# veils_v40.net
KiCad netlist of a schematic drawn in EAGLE
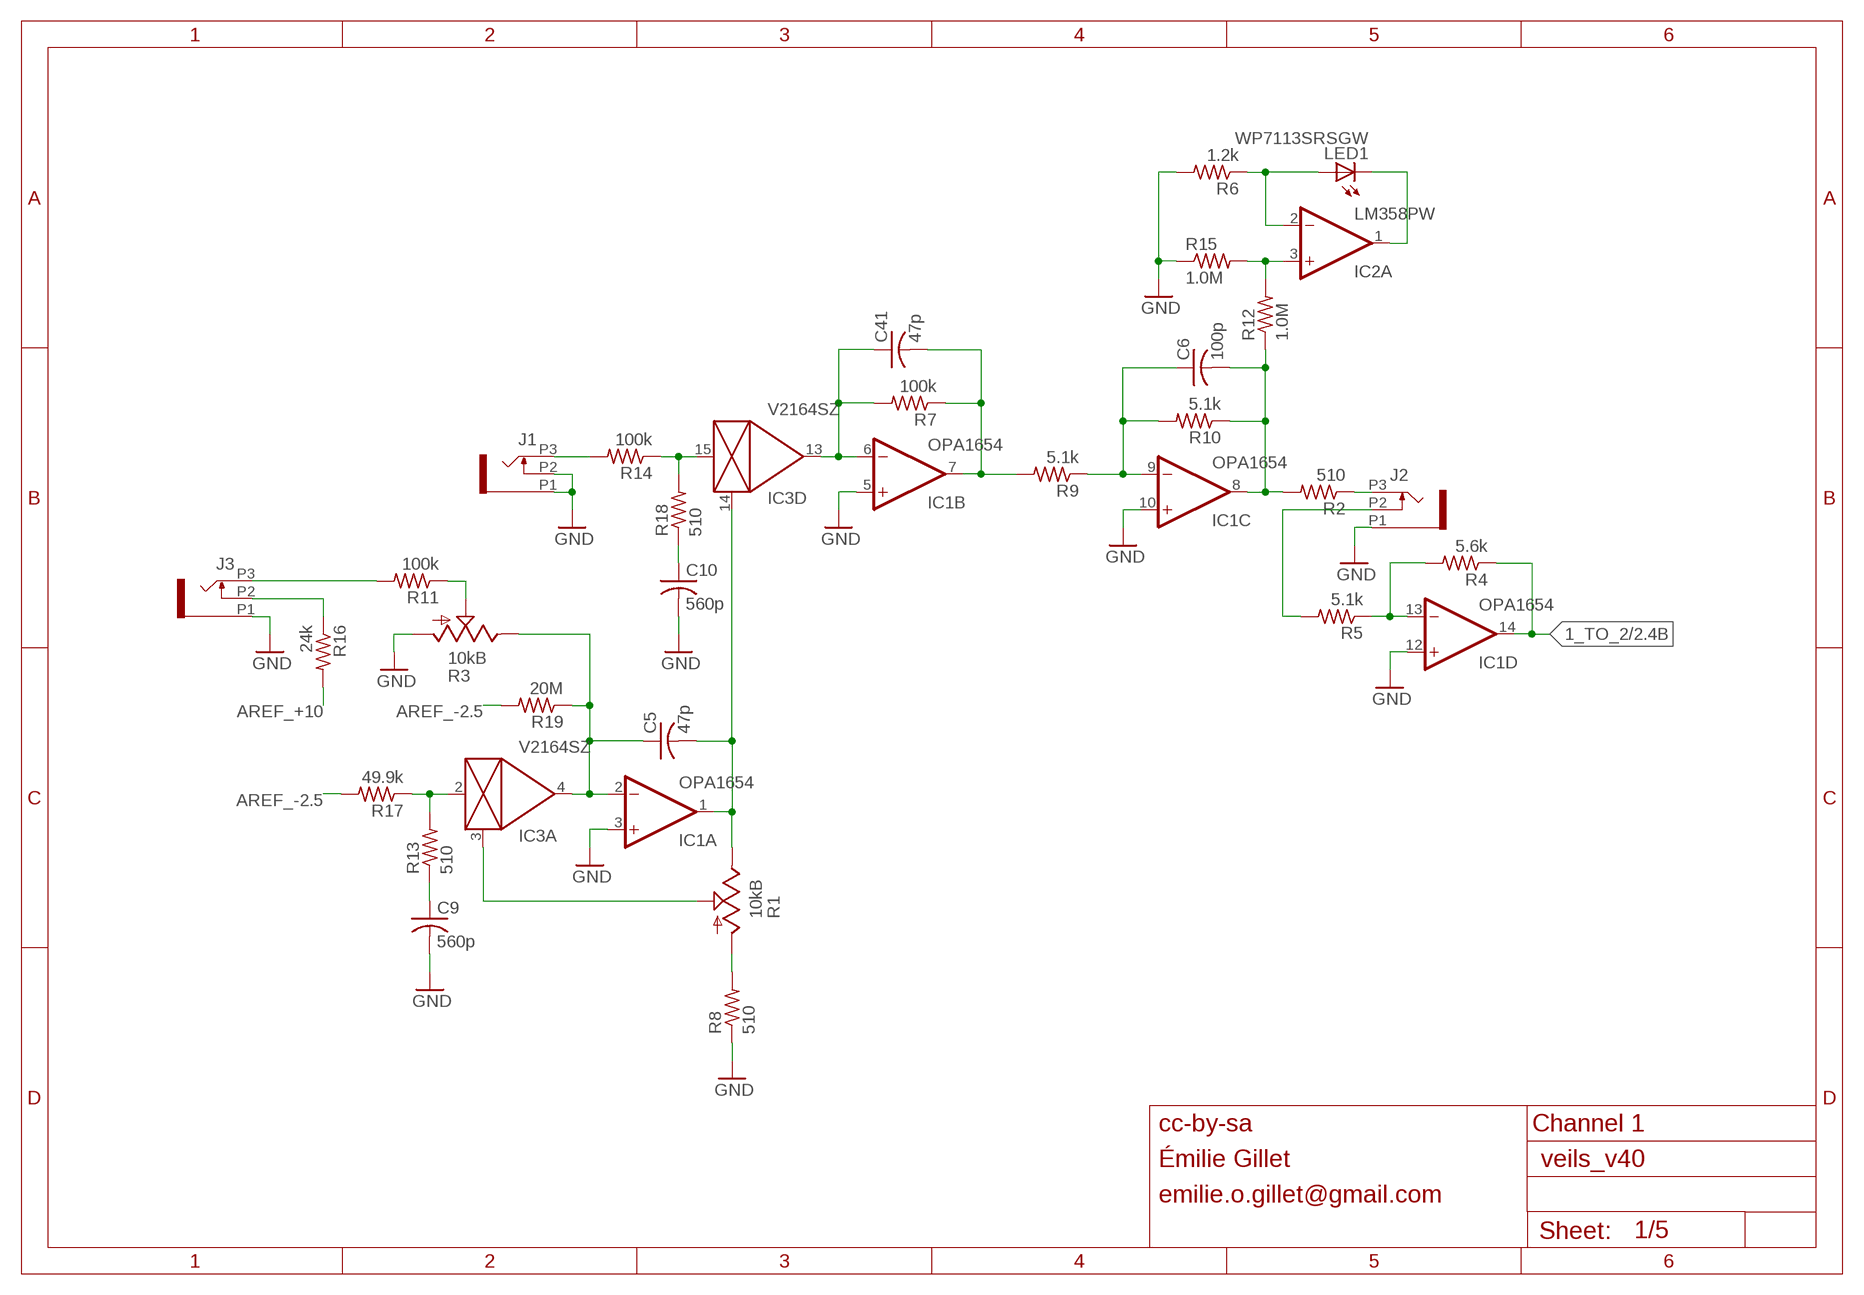
[diagram p0: schematic, sheet 1]
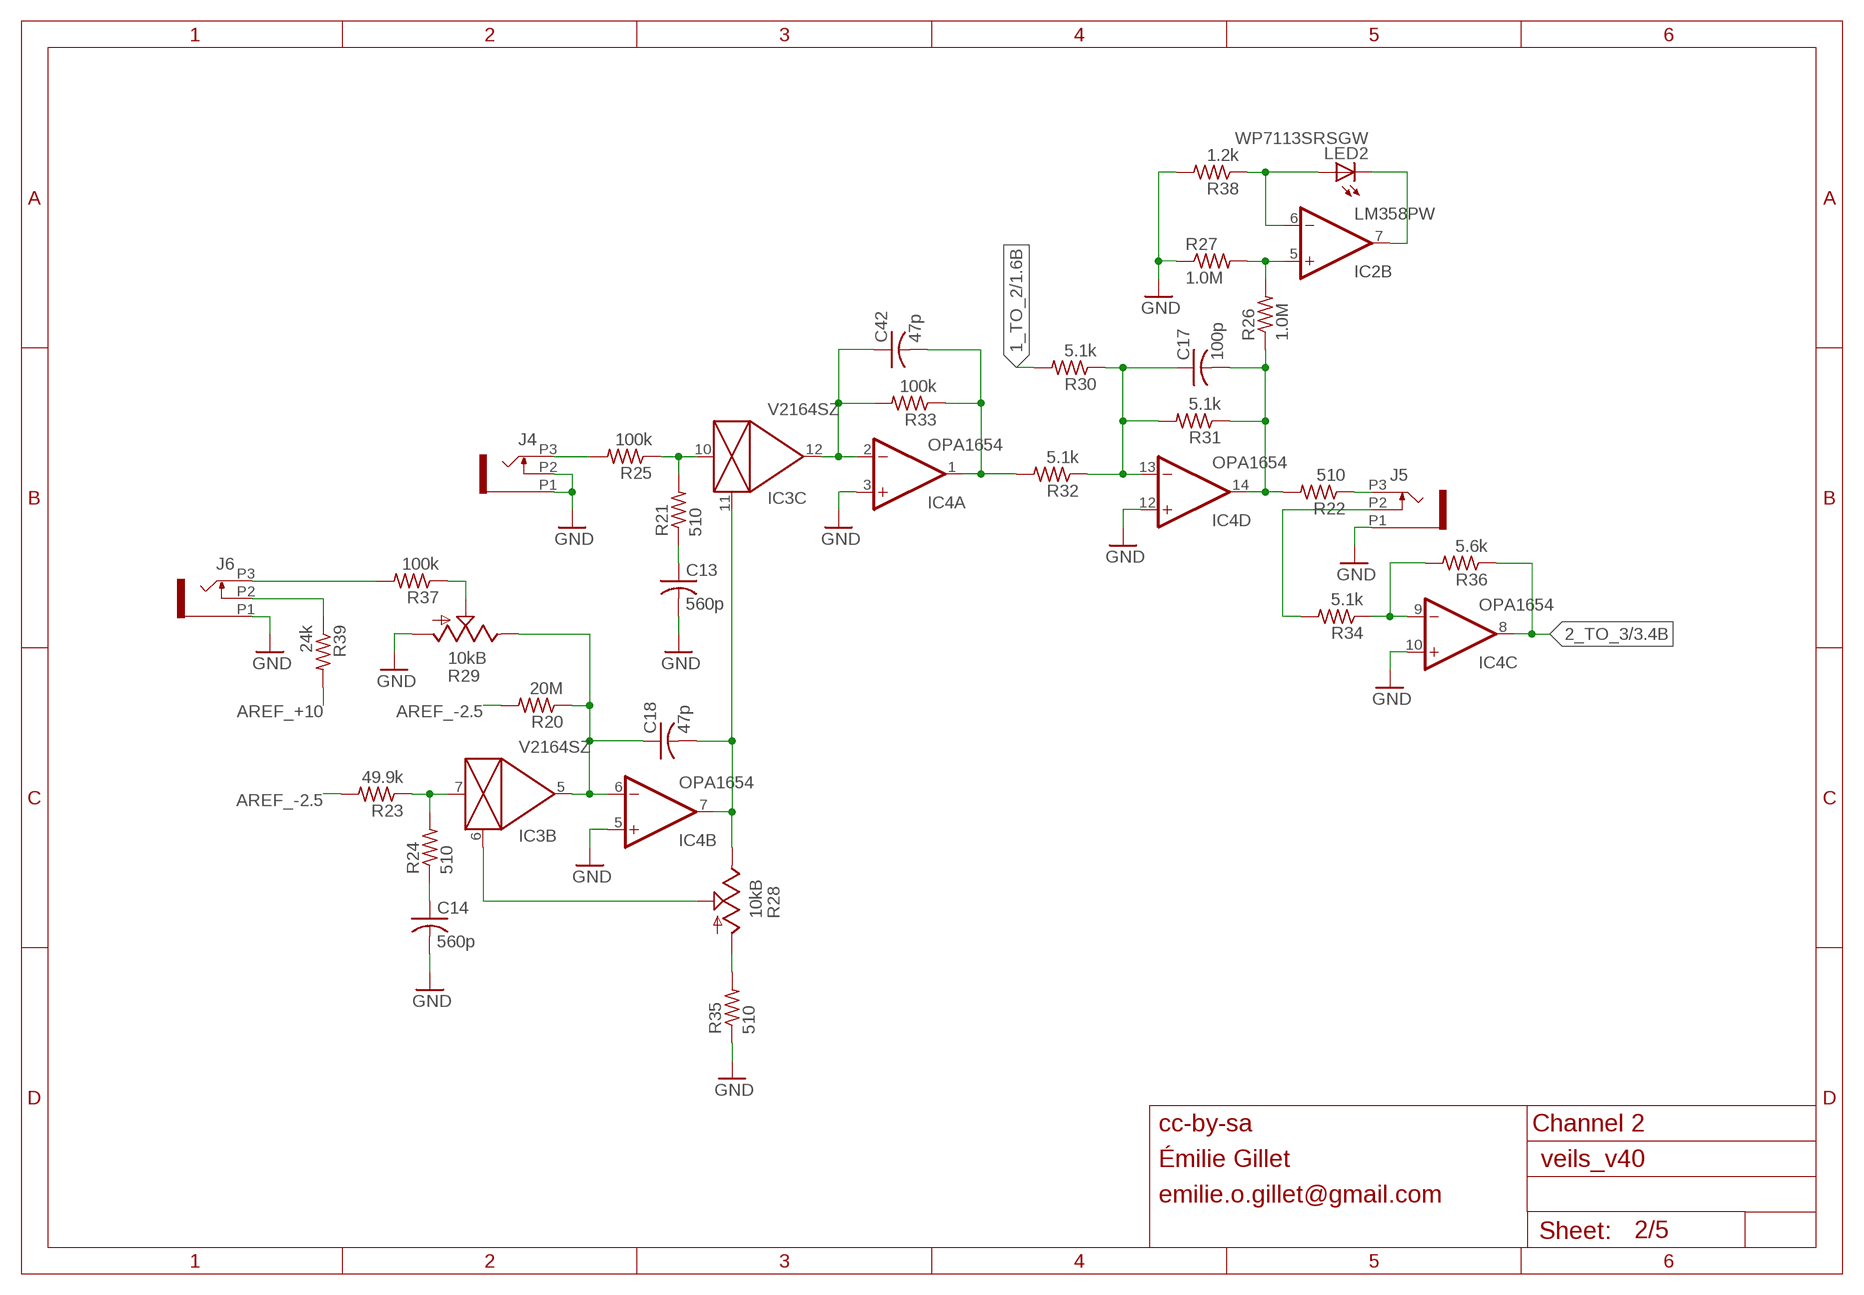
[diagram p1: schematic, sheet 2]
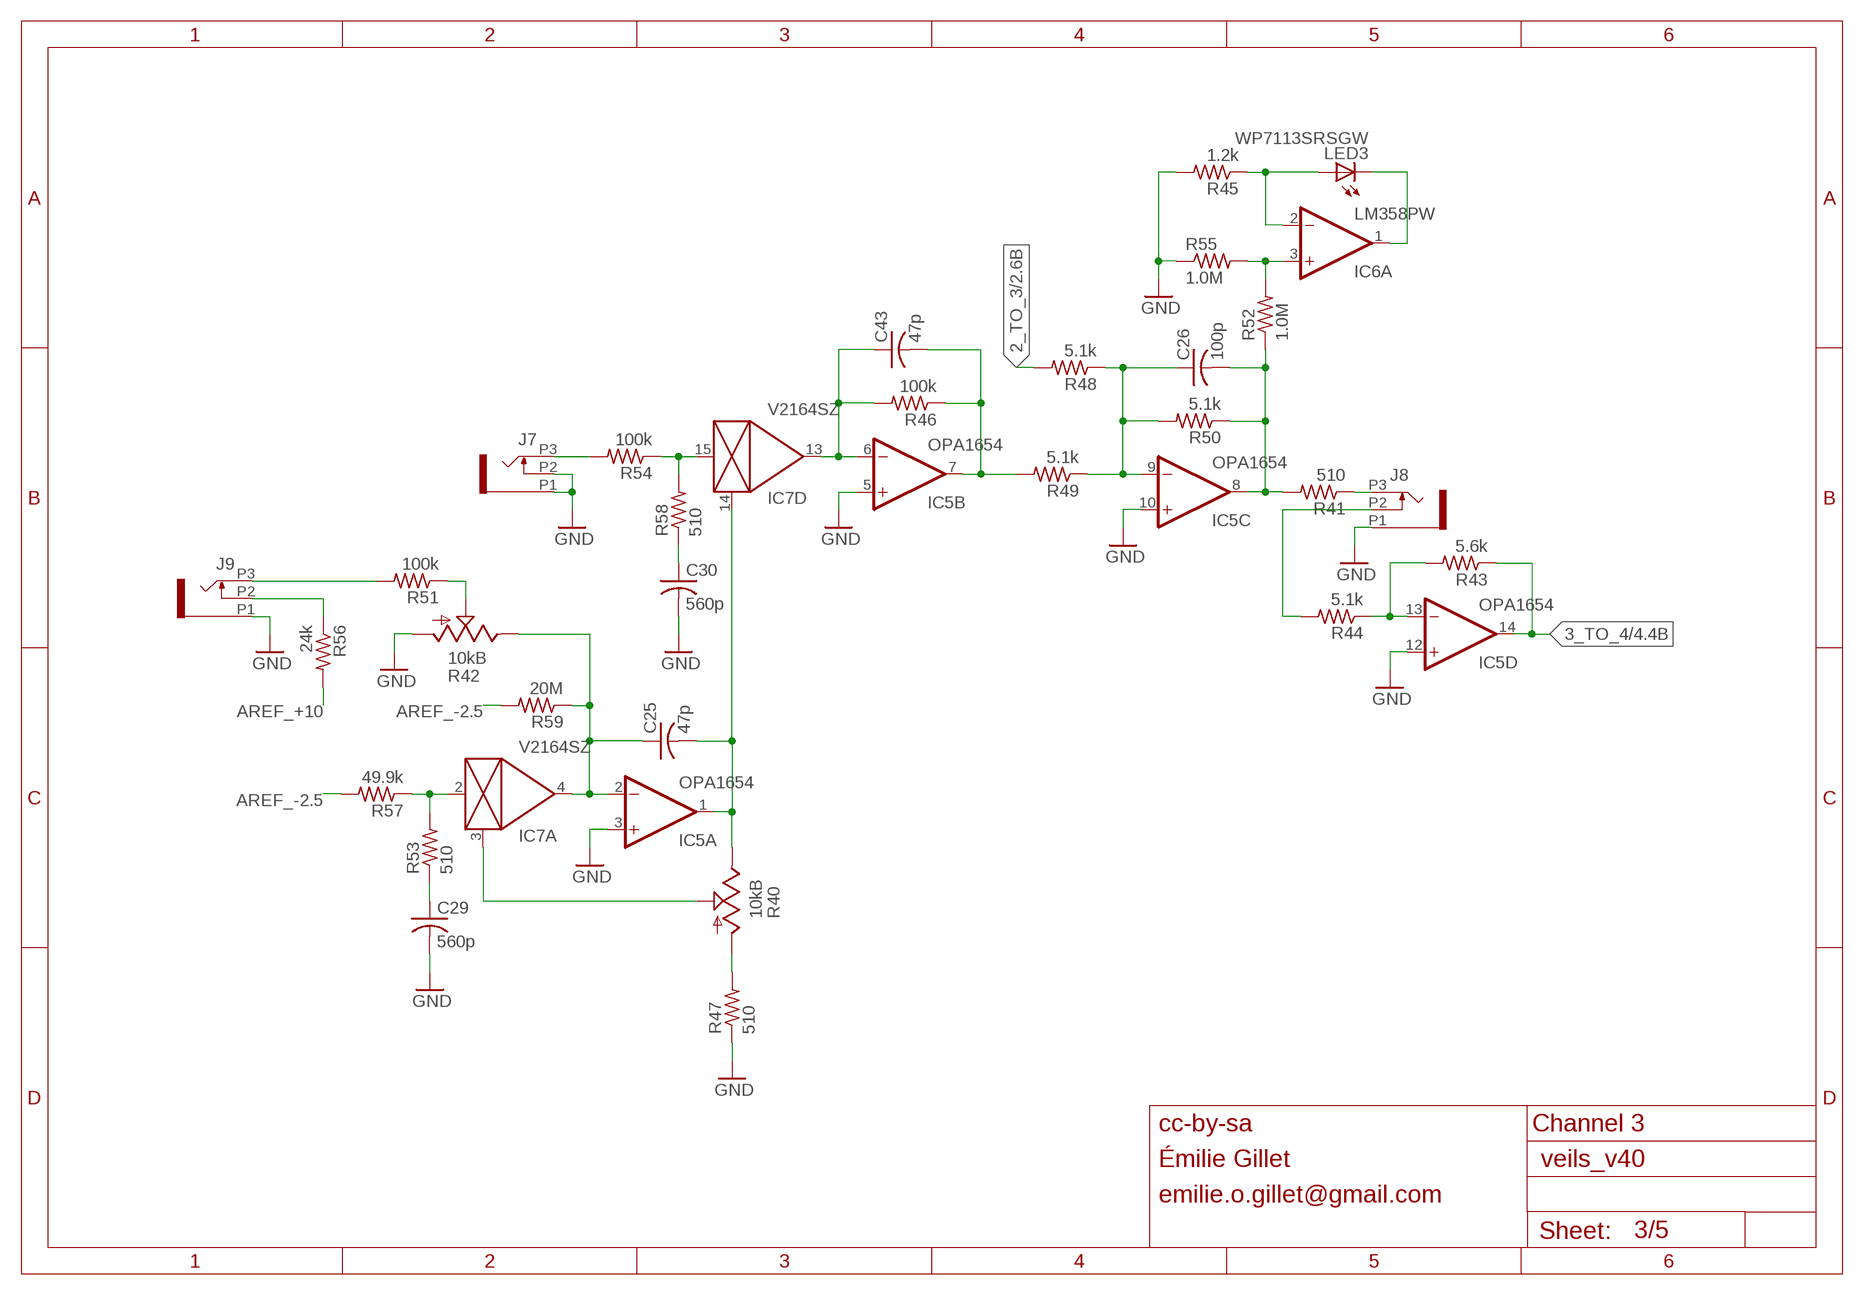
[diagram p2: schematic, sheet 3]
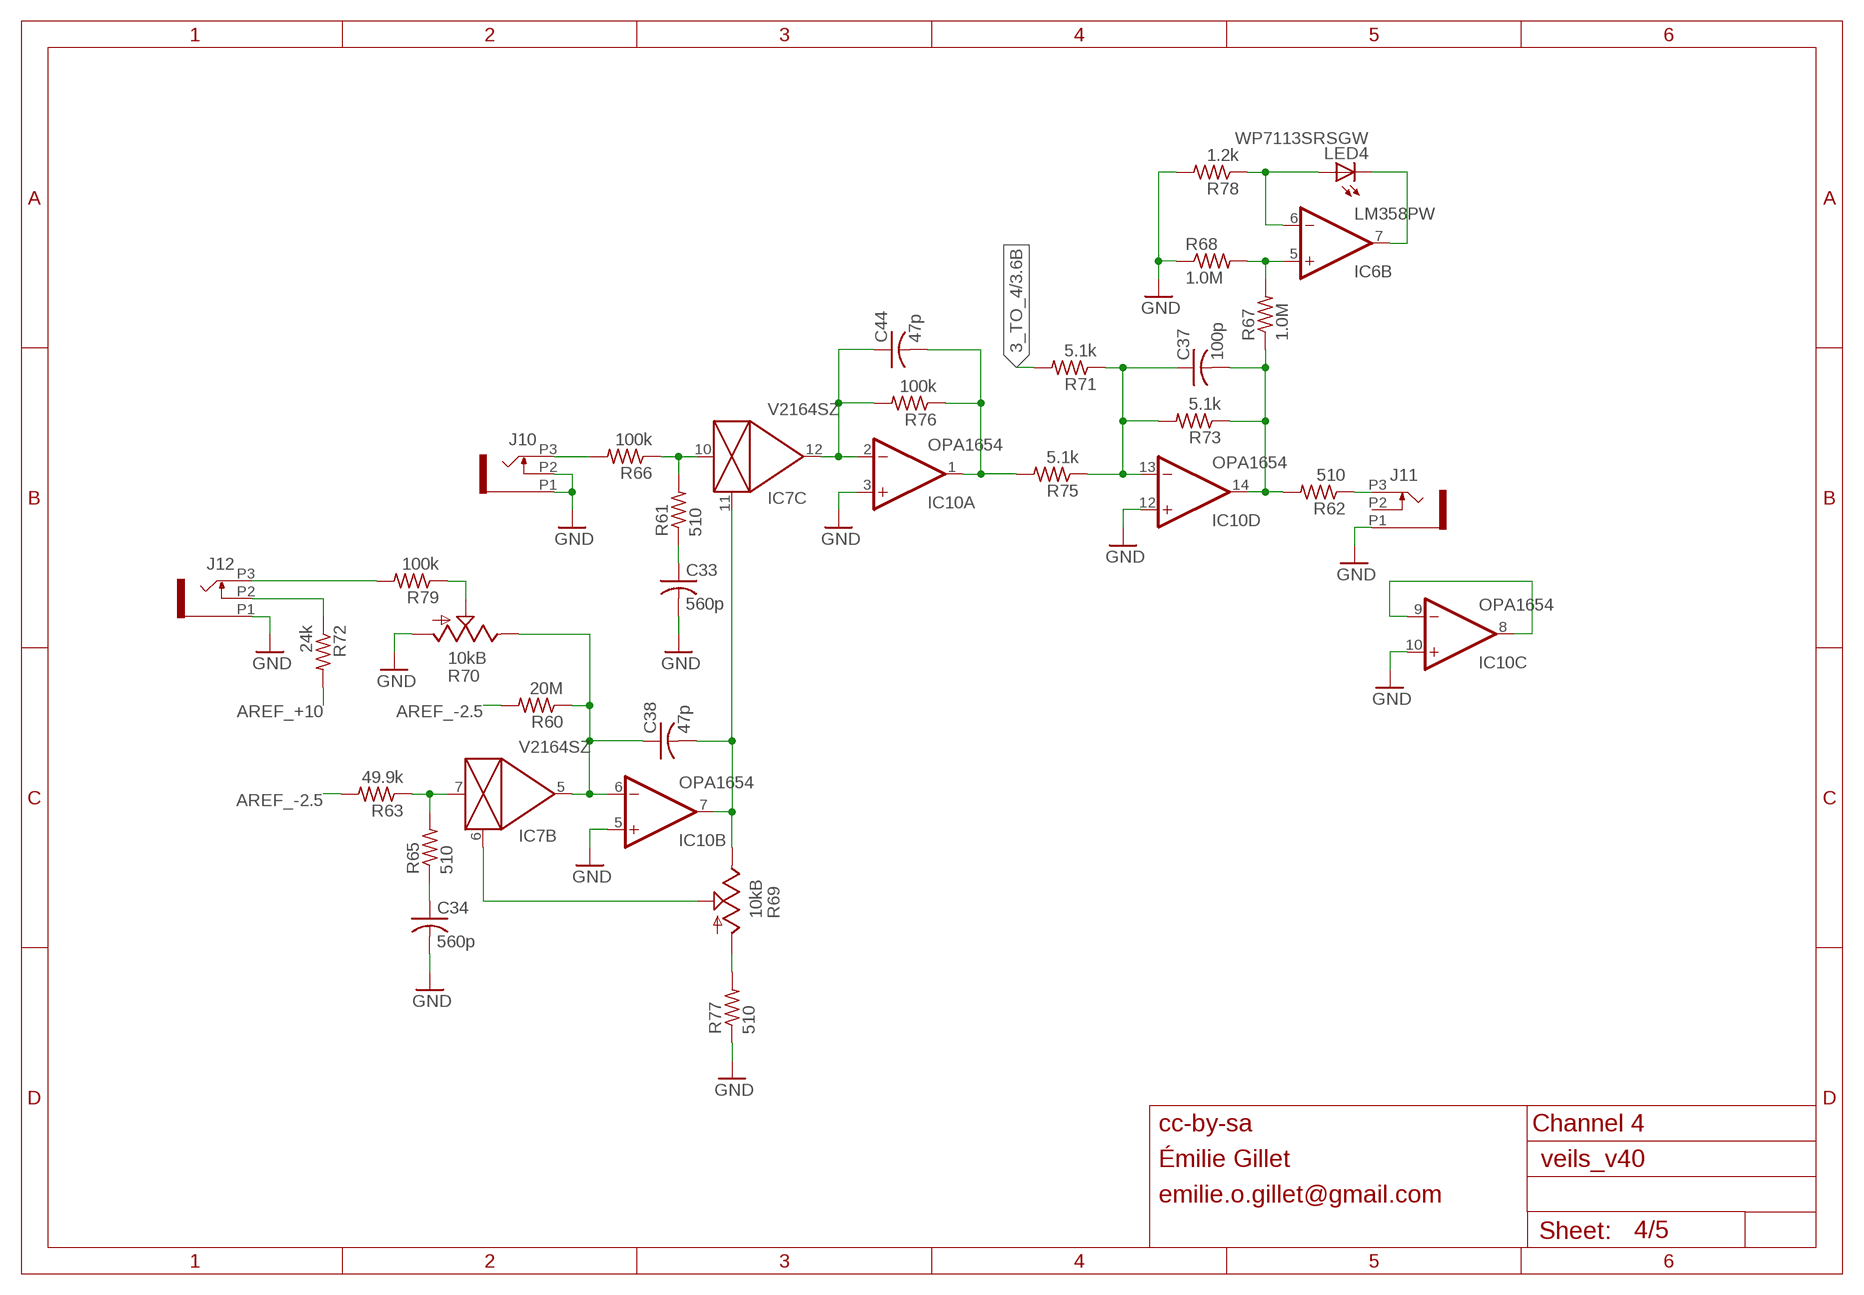
[diagram p3: schematic, sheet 4]
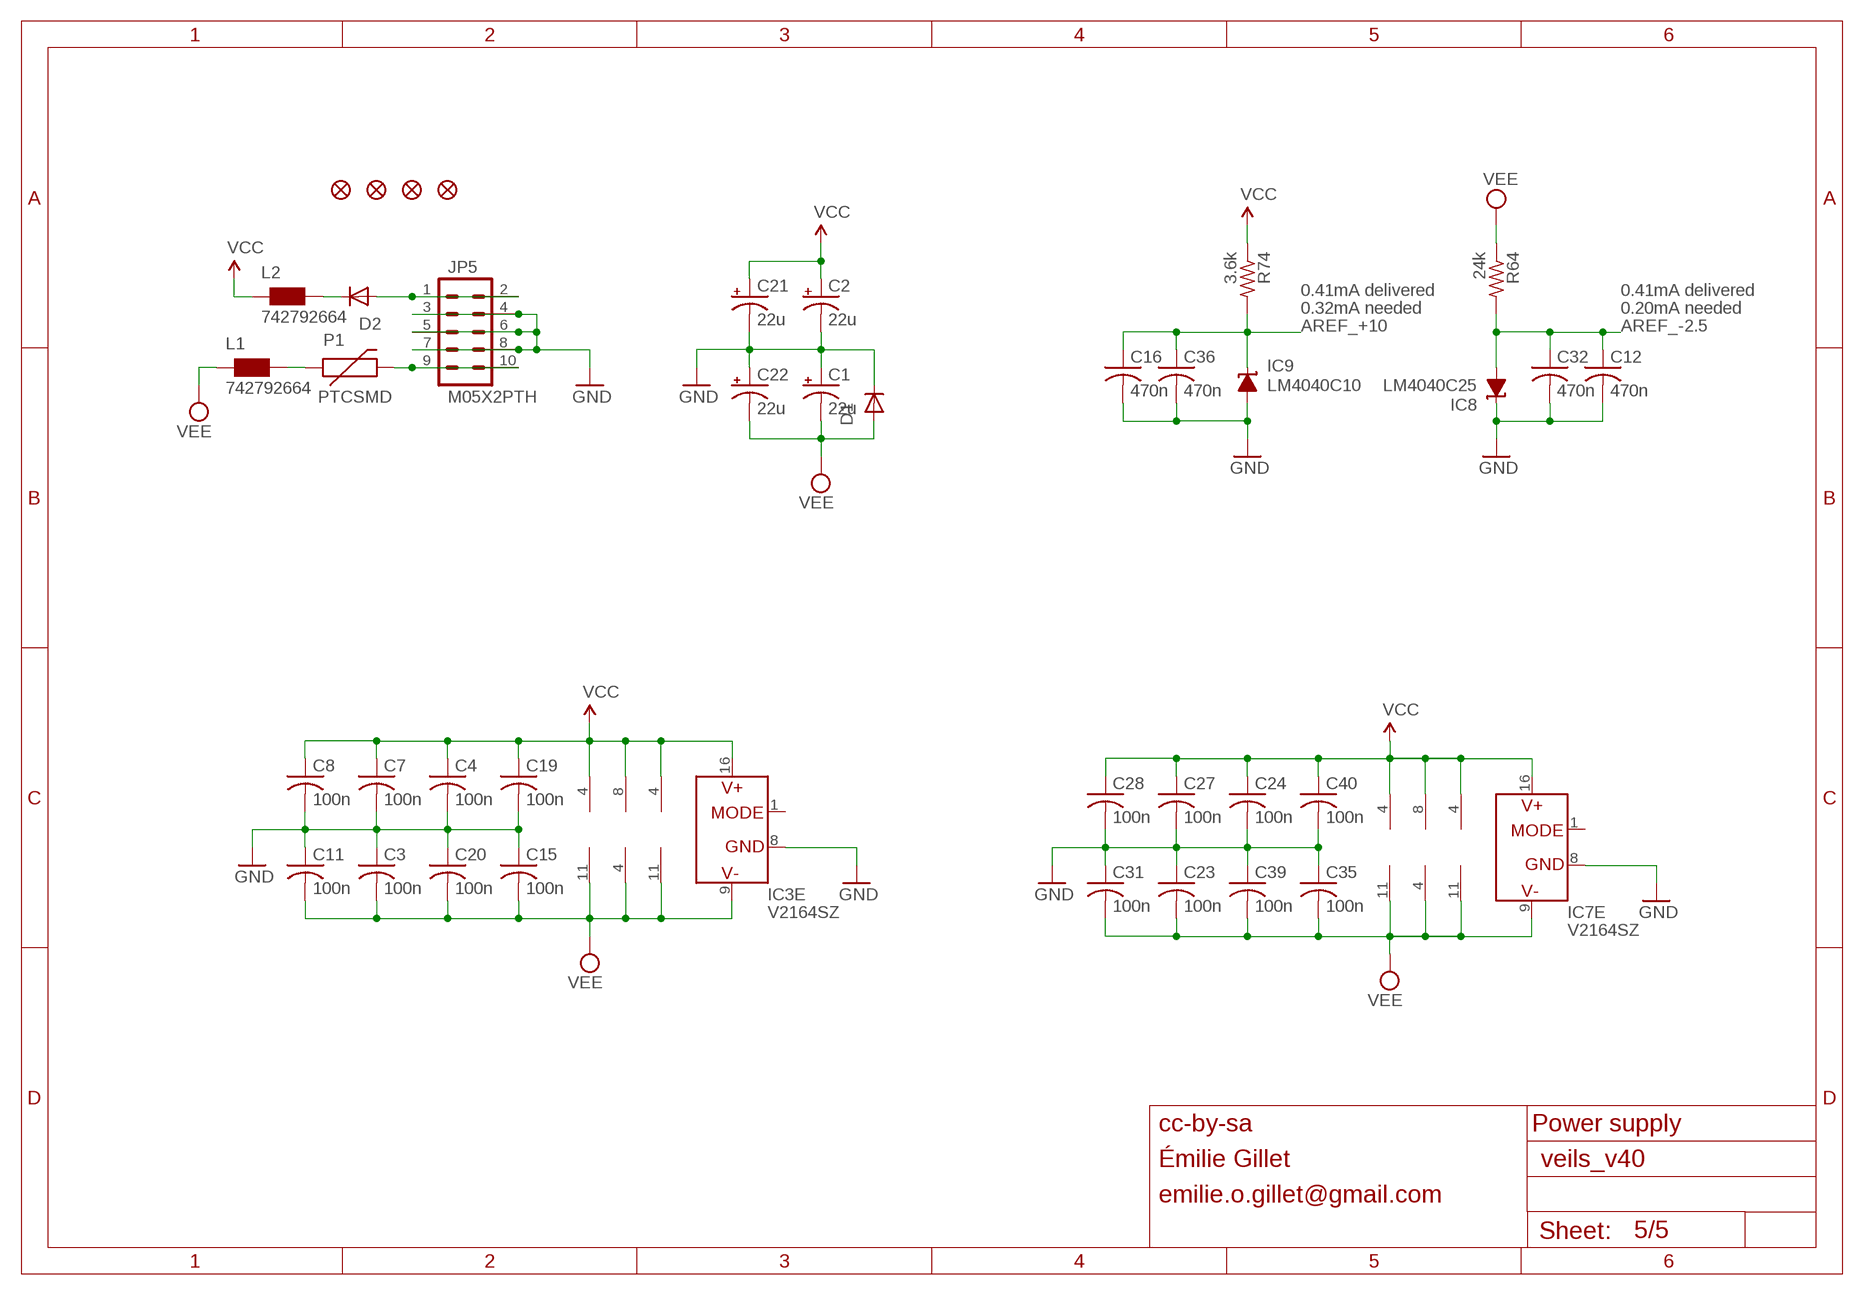
[diagram p4: schematic, sheet 5]

(export (version "E")
  (design (tool "Eeschema 10.0.6"))
  (components
    (comp (ref "C13")
      (value "560p")
      (footprint "eagle-import:C0402")
      (libsource (lib "eagle-import") (part "C-USC0402"))
    )
    (comp (ref "C14")
      (value "560p")
      (footprint "eagle-import:C0402")
      (libsource (lib "eagle-import") (part "C-USC0402"))
    )
    (comp (ref "C17")
      (value "100p")
      (footprint "eagle-import:C0402")
      (libsource (lib "eagle-import") (part "C-USC0402"))
    )
    (comp (ref "C18")
      (value "47p")
      (footprint "eagle-import:C0402")
      (libsource (lib "eagle-import") (part "C-USC0402"))
    )
    (comp (ref "C42")
      (value "47p")
      (footprint "eagle-import:C0402")
      (libsource (lib "eagle-import") (part "C-USC0402"))
    )
    (comp (ref "IC2")
      (value "LM358PW")
      (footprint "eagle-import:TSSOP8")
      (libsource (lib "eagle-import") (part "TL072PW"))
    )
    (comp (ref "IC3")
      (value "V2164SZ")
      (footprint "eagle-import:SOIC16N")
      (libsource (lib "eagle-import") (part "SSM2164S"))
    )
    (comp (ref "IC4")
      (value "OPA1654")
      (footprint "eagle-import:TSSOP14")
      (libsource (lib "eagle-import") (part "TL074PW"))
    )
    (comp (ref "J4")
      (value "PJ301_THONKICONN6")
      (footprint "eagle-import:WQP_PJ_301M6")
      (libsource (lib "eagle-import") (part "PJ301_THONKICONN6"))
    )
    (comp (ref "J5")
      (value "PJ301_THONKICONN6")
      (footprint "eagle-import:WQP_PJ_301M6")
      (libsource (lib "eagle-import") (part "PJ301_THONKICONN6"))
    )
    (comp (ref "J6")
      (value "PJ301_THONKICONN6")
      (footprint "eagle-import:WQP_PJ_301M6")
      (libsource (lib "eagle-import") (part "PJ301_THONKICONN6"))
    )
    (comp (ref "LED2")
      (value "WP7113SRSGW")
      (footprint "eagle-import:LED5MM")
      (libsource (lib "eagle-import") (part "LED5MM"))
    )
    (comp (ref "R20")
      (value "20M")
      (footprint "eagle-import:R0402")
      (libsource (lib "eagle-import") (part "R-US_R0402"))
    )
    (comp (ref "R21")
      (value "510")
      (footprint "eagle-import:R0402")
      (libsource (lib "eagle-import") (part "R-US_R0402"))
    )
    (comp (ref "R22")
      (value "510")
      (footprint "eagle-import:R0402")
      (libsource (lib "eagle-import") (part "R-US_R0402"))
    )
    (comp (ref "R23")
      (value "49.9k")
      (footprint "eagle-import:R0402")
      (libsource (lib "eagle-import") (part "R-US_R0402"))
    )
    (comp (ref "R24")
      (value "510")
      (footprint "eagle-import:R0402")
      (libsource (lib "eagle-import") (part "R-US_R0402"))
    )
    (comp (ref "R25")
      (value "100k")
      (footprint "eagle-import:R0402")
      (libsource (lib "eagle-import") (part "R-US_R0402"))
    )
    (comp (ref "R26")
      (value "1.0M")
      (footprint "eagle-import:R0402")
      (libsource (lib "eagle-import") (part "R-US_R0402"))
    )
    (comp (ref "R27")
      (value "1.0M")
      (footprint "eagle-import:R0402")
      (libsource (lib "eagle-import") (part "R-US_R0402"))
    )
    (comp (ref "R28")
      (value "10kB")
      (footprint "eagle-import:ALPS_POT_VERTICAL")
      (libsource (lib "eagle-import") (part "POT_USVERTICAL"))
    )
    (comp (ref "R29")
      (value "10kB")
      (footprint "eagle-import:ALPS_POT_VERTICAL_PS")
      (libsource (lib "eagle-import") (part "pot-alps_POT_USVERTICAL_PS"))
    )
    (comp (ref "R30")
      (value "5.1k")
      (footprint "eagle-import:R0402")
      (libsource (lib "eagle-import") (part "R-US_R0402"))
    )
    (comp (ref "R31")
      (value "5.1k")
      (footprint "eagle-import:R0402")
      (libsource (lib "eagle-import") (part "R-US_R0402"))
    )
    (comp (ref "R32")
      (value "5.1k")
      (footprint "eagle-import:R0402")
      (libsource (lib "eagle-import") (part "R-US_R0402"))
    )
    (comp (ref "R33")
      (value "100k")
      (footprint "eagle-import:R0402")
      (libsource (lib "eagle-import") (part "R-US_R0402"))
    )
    (comp (ref "R34")
      (value "5.1k")
      (footprint "eagle-import:R0402")
      (libsource (lib "eagle-import") (part "R-US_R0402"))
    )
    (comp (ref "R35")
      (value "510")
      (footprint "eagle-import:R0402")
      (libsource (lib "eagle-import") (part "R-US_R0402"))
    )
    (comp (ref "R36")
      (value "5.6k")
      (footprint "eagle-import:R0402")
      (libsource (lib "eagle-import") (part "R-US_R0402"))
    )
    (comp (ref "R37")
      (value "100k")
      (footprint "eagle-import:R0402")
      (libsource (lib "eagle-import") (part "R-US_R0402"))
    )
    (comp (ref "R38")
      (value "1.2k")
      (footprint "eagle-import:R0402")
      (libsource (lib "eagle-import") (part "R-US_R0402"))
    )
    (comp (ref "R39")
      (value "24k")
      (footprint "eagle-import:R0402")
      (libsource (lib "eagle-import") (part "R-US_R0402"))
    )
    (comp (ref "C5")
      (value "47p")
      (footprint "eagle-import:C0402")
      (libsource (lib "eagle-import") (part "C-USC0402"))
    )
    (comp (ref "C6")
      (value "100p")
      (footprint "eagle-import:C0402")
      (libsource (lib "eagle-import") (part "C-USC0402"))
    )
    (comp (ref "C9")
      (value "560p")
      (footprint "eagle-import:C0402")
      (libsource (lib "eagle-import") (part "C-USC0402"))
    )
    (comp (ref "C10")
      (value "560p")
      (footprint "eagle-import:C0402")
      (libsource (lib "eagle-import") (part "C-USC0402"))
    )
    (comp (ref "C41")
      (value "47p")
      (footprint "eagle-import:C0402")
      (libsource (lib "eagle-import") (part "C-USC0402"))
    )
    (comp (ref "IC1")
      (value "OPA1654")
      (footprint "eagle-import:TSSOP14")
      (libsource (lib "eagle-import") (part "TL074PW"))
    )
    (comp (ref "J1")
      (value "PJ301_THONKICONN6")
      (footprint "eagle-import:WQP_PJ_301M6")
      (libsource (lib "eagle-import") (part "PJ301_THONKICONN6"))
    )
    (comp (ref "J2")
      (value "PJ301_THONKICONN6")
      (footprint "eagle-import:WQP_PJ_301M6")
      (libsource (lib "eagle-import") (part "PJ301_THONKICONN6"))
    )
    (comp (ref "J3")
      (value "PJ301_THONKICONN6")
      (footprint "eagle-import:WQP_PJ_301M6")
      (libsource (lib "eagle-import") (part "PJ301_THONKICONN6"))
    )
    (comp (ref "LED1")
      (value "WP7113SRSGW")
      (footprint "eagle-import:LED5MM")
      (libsource (lib "eagle-import") (part "LED5MM"))
    )
    (comp (ref "R1")
      (value "10kB")
      (footprint "eagle-import:ALPS_POT_VERTICAL")
      (libsource (lib "eagle-import") (part "POT_USVERTICAL"))
    )
    (comp (ref "R2")
      (value "510")
      (footprint "eagle-import:R0402")
      (libsource (lib "eagle-import") (part "R-US_R0402"))
    )
    (comp (ref "R3")
      (value "10kB")
      (footprint "eagle-import:ALPS_POT_VERTICAL_PS")
      (libsource (lib "eagle-import") (part "pot-alps_POT_USVERTICAL_PS"))
    )
    (comp (ref "R4")
      (value "5.6k")
      (footprint "eagle-import:R0402")
      (libsource (lib "eagle-import") (part "R-US_R0402"))
    )
    (comp (ref "R5")
      (value "5.1k")
      (footprint "eagle-import:R0402")
      (libsource (lib "eagle-import") (part "R-US_R0402"))
    )
    (comp (ref "R6")
      (value "1.2k")
      (footprint "eagle-import:R0402")
      (libsource (lib "eagle-import") (part "R-US_R0402"))
    )
    (comp (ref "R7")
      (value "100k")
      (footprint "eagle-import:R0402")
      (libsource (lib "eagle-import") (part "R-US_R0402"))
    )
    (comp (ref "R8")
      (value "510")
      (footprint "eagle-import:R0402")
      (libsource (lib "eagle-import") (part "R-US_R0402"))
    )
    (comp (ref "R9")
      (value "5.1k")
      (footprint "eagle-import:R0402")
      (libsource (lib "eagle-import") (part "R-US_R0402"))
    )
    (comp (ref "R10")
      (value "5.1k")
      (footprint "eagle-import:R0402")
      (libsource (lib "eagle-import") (part "R-US_R0402"))
    )
    (comp (ref "R11")
      (value "100k")
      (footprint "eagle-import:R0402")
      (libsource (lib "eagle-import") (part "R-US_R0402"))
    )
    (comp (ref "R12")
      (value "1.0M")
      (footprint "eagle-import:R0402")
      (libsource (lib "eagle-import") (part "R-US_R0402"))
    )
    (comp (ref "R13")
      (value "510")
      (footprint "eagle-import:R0402")
      (libsource (lib "eagle-import") (part "R-US_R0402"))
    )
    (comp (ref "R14")
      (value "100k")
      (footprint "eagle-import:R0402")
      (libsource (lib "eagle-import") (part "R-US_R0402"))
    )
    (comp (ref "R15")
      (value "1.0M")
      (footprint "eagle-import:R0402")
      (libsource (lib "eagle-import") (part "R-US_R0402"))
    )
    (comp (ref "R16")
      (value "24k")
      (footprint "eagle-import:R0402")
      (libsource (lib "eagle-import") (part "R-US_R0402"))
    )
    (comp (ref "R17")
      (value "49.9k")
      (footprint "eagle-import:R0402")
      (libsource (lib "eagle-import") (part "R-US_R0402"))
    )
    (comp (ref "R18")
      (value "510")
      (footprint "eagle-import:R0402")
      (libsource (lib "eagle-import") (part "R-US_R0402"))
    )
    (comp (ref "R19")
      (value "20M")
      (footprint "eagle-import:R0402")
      (libsource (lib "eagle-import") (part "R-US_R0402"))
    )
    (comp (ref "C1")
      (value "22u")
      (footprint "eagle-import:PANASONIC_B")
      (libsource (lib "eagle-import") (part "CPOL-USB"))
    )
    (comp (ref "C2")
      (value "22u")
      (footprint "eagle-import:PANASONIC_B")
      (libsource (lib "eagle-import") (part "CPOL-USB"))
    )
    (comp (ref "C3")
      (value "100n")
      (footprint "eagle-import:C0402")
      (libsource (lib "eagle-import") (part "C-USC0402"))
    )
    (comp (ref "C4")
      (value "100n")
      (footprint "eagle-import:C0402")
      (libsource (lib "eagle-import") (part "C-USC0402"))
    )
    (comp (ref "C7")
      (value "100n")
      (footprint "eagle-import:C0402")
      (libsource (lib "eagle-import") (part "C-USC0402"))
    )
    (comp (ref "C8")
      (value "100n")
      (footprint "eagle-import:C0402")
      (libsource (lib "eagle-import") (part "C-USC0402"))
    )
    (comp (ref "C11")
      (value "100n")
      (footprint "eagle-import:C0402")
      (libsource (lib "eagle-import") (part "C-USC0402"))
    )
    (comp (ref "C12")
      (value "470n")
      (footprint "eagle-import:C0402")
      (libsource (lib "eagle-import") (part "C-USC0402"))
    )
    (comp (ref "C15")
      (value "100n")
      (footprint "eagle-import:C0402")
      (libsource (lib "eagle-import") (part "C-USC0402"))
    )
    (comp (ref "C16")
      (value "470n")
      (footprint "eagle-import:C0402")
      (libsource (lib "eagle-import") (part "C-USC0402"))
    )
    (comp (ref "C19")
      (value "100n")
      (footprint "eagle-import:C0402")
      (libsource (lib "eagle-import") (part "C-USC0402"))
    )
    (comp (ref "C20")
      (value "100n")
      (footprint "eagle-import:C0402")
      (libsource (lib "eagle-import") (part "C-USC0402"))
    )
    (comp (ref "C21")
      (value "22u")
      (footprint "eagle-import:PANASONIC_B")
      (libsource (lib "eagle-import") (part "CPOL-USB"))
    )
    (comp (ref "C22")
      (value "22u")
      (footprint "eagle-import:PANASONIC_B")
      (libsource (lib "eagle-import") (part "CPOL-USB"))
    )
    (comp (ref "C23")
      (value "100n")
      (footprint "eagle-import:C0402")
      (libsource (lib "eagle-import") (part "C-USC0402"))
    )
    (comp (ref "C24")
      (value "100n")
      (footprint "eagle-import:C0402")
      (libsource (lib "eagle-import") (part "C-USC0402"))
    )
    (comp (ref "C27")
      (value "100n")
      (footprint "eagle-import:C0402")
      (libsource (lib "eagle-import") (part "C-USC0402"))
    )
    (comp (ref "C28")
      (value "100n")
      (footprint "eagle-import:C0402")
      (libsource (lib "eagle-import") (part "C-USC0402"))
    )
    (comp (ref "C31")
      (value "100n")
      (footprint "eagle-import:C0402")
      (libsource (lib "eagle-import") (part "C-USC0402"))
    )
    (comp (ref "C32")
      (value "470n")
      (footprint "eagle-import:C0402")
      (libsource (lib "eagle-import") (part "C-USC0402"))
    )
    (comp (ref "C35")
      (value "100n")
      (footprint "eagle-import:C0402")
      (libsource (lib "eagle-import") (part "C-USC0402"))
    )
    (comp (ref "C36")
      (value "470n")
      (footprint "eagle-import:C0402")
      (libsource (lib "eagle-import") (part "C-USC0402"))
    )
    (comp (ref "C39")
      (value "100n")
      (footprint "eagle-import:C0402")
      (libsource (lib "eagle-import") (part "C-USC0402"))
    )
    (comp (ref "C40")
      (value "100n")
      (footprint "eagle-import:C0402")
      (libsource (lib "eagle-import") (part "C-USC0402"))
    )
    (comp (ref "D1")
      (value "1N5819HW")
      (footprint "eagle-import:SOD123")
      (libsource (lib "eagle-import") (part "DIODE-SOD123"))
    )
    (comp (ref "D2")
      (value "1N5819HW")
      (footprint "eagle-import:SOD123")
      (libsource (lib "eagle-import") (part "DIODE-SOD123"))
    )
    (comp (ref "IC5")
      (value "OPA1654")
      (footprint "eagle-import:TSSOP14")
      (libsource (lib "eagle-import") (part "TL074PW"))
    )
    (comp (ref "IC6")
      (value "LM358PW")
      (footprint "eagle-import:TSSOP8")
      (libsource (lib "eagle-import") (part "TL072PW"))
    )
    (comp (ref "IC7")
      (value "V2164SZ")
      (footprint "eagle-import:SOIC16N")
      (libsource (lib "eagle-import") (part "SSM2164S"))
    )
    (comp (ref "IC8")
      (value "LM4040C25")
      (footprint "eagle-import:DBZ_R-PDSO-G3")
      (libsource (lib "eagle-import") (part "LM4041DBZB12"))
    )
    (comp (ref "IC9")
      (value "LM4040C10")
      (footprint "eagle-import:DBZ_R-PDSO-G3")
      (libsource (lib "eagle-import") (part "LM4041DBZB12"))
    )
    (comp (ref "IC10")
      (value "OPA1654")
      (footprint "eagle-import:TSSOP14")
      (libsource (lib "eagle-import") (part "TL074PW"))
    )
    (comp (ref "JP1")
      (value "FIDUCIAL1X2")
      (footprint "eagle-import:FIDUCIAL-1X2")
      (libsource (lib "eagle-import") (part "FIDUCIAL1X2"))
    )
    (comp (ref "JP2")
      (value "FIDUCIAL1X2")
      (footprint "eagle-import:FIDUCIAL-1X2")
      (libsource (lib "eagle-import") (part "FIDUCIAL1X2"))
    )
    (comp (ref "JP3")
      (value "FIDUCIAL1X2")
      (footprint "eagle-import:FIDUCIAL-1X2")
      (libsource (lib "eagle-import") (part "FIDUCIAL1X2"))
    )
    (comp (ref "JP4")
      (value "FIDUCIAL1X2")
      (footprint "eagle-import:FIDUCIAL-1X2")
      (libsource (lib "eagle-import") (part "FIDUCIAL1X2"))
    )
    (comp (ref "JP5")
      (value "M05X2PTH")
      (footprint "eagle-import:AVR_ICSP")
      (libsource (lib "eagle-import") (part "M05X2PTH"))
    )
    (comp (ref "L1")
      (value "742792664")
      (footprint "eagle-import:0603")
      (libsource (lib "eagle-import") (part "WE-CBF_0603"))
    )
    (comp (ref "L2")
      (value "742792664")
      (footprint "eagle-import:0603")
      (libsource (lib "eagle-import") (part "WE-CBF_0603"))
    )
    (comp (ref "P1")
      (value "PTCSMD")
      (footprint "eagle-import:PTC-1206")
      (libsource (lib "eagle-import") (part "PTCSMD"))
    )
    (comp (ref "R64")
      (value "24k")
      (footprint "eagle-import:R0402")
      (libsource (lib "eagle-import") (part "R-US_R0402"))
    )
    (comp (ref "R74")
      (value "3.6k")
      (footprint "eagle-import:R0402")
      (libsource (lib "eagle-import") (part "R-US_R0402"))
    )
    (comp (ref "C25")
      (value "47p")
      (footprint "eagle-import:C0402")
      (libsource (lib "eagle-import") (part "C-USC0402"))
    )
    (comp (ref "C26")
      (value "100p")
      (footprint "eagle-import:C0402")
      (libsource (lib "eagle-import") (part "C-USC0402"))
    )
    (comp (ref "C29")
      (value "560p")
      (footprint "eagle-import:C0402")
      (libsource (lib "eagle-import") (part "C-USC0402"))
    )
    (comp (ref "C30")
      (value "560p")
      (footprint "eagle-import:C0402")
      (libsource (lib "eagle-import") (part "C-USC0402"))
    )
    (comp (ref "C43")
      (value "47p")
      (footprint "eagle-import:C0402")
      (libsource (lib "eagle-import") (part "C-USC0402"))
    )
    (comp (ref "J7")
      (value "PJ301_THONKICONN6")
      (footprint "eagle-import:WQP_PJ_301M6")
      (libsource (lib "eagle-import") (part "PJ301_THONKICONN6"))
    )
    (comp (ref "J8")
      (value "PJ301_THONKICONN6")
      (footprint "eagle-import:WQP_PJ_301M6")
      (libsource (lib "eagle-import") (part "PJ301_THONKICONN6"))
    )
    (comp (ref "J9")
      (value "PJ301_THONKICONN6")
      (footprint "eagle-import:WQP_PJ_301M6")
      (libsource (lib "eagle-import") (part "PJ301_THONKICONN6"))
    )
    (comp (ref "LED3")
      (value "WP7113SRSGW")
      (footprint "eagle-import:LED5MM")
      (libsource (lib "eagle-import") (part "LED5MM"))
    )
    (comp (ref "R40")
      (value "10kB")
      (footprint "eagle-import:ALPS_POT_VERTICAL")
      (libsource (lib "eagle-import") (part "POT_USVERTICAL"))
    )
    (comp (ref "R41")
      (value "510")
      (footprint "eagle-import:R0402")
      (libsource (lib "eagle-import") (part "R-US_R0402"))
    )
    (comp (ref "R42")
      (value "10kB")
      (footprint "eagle-import:ALPS_POT_VERTICAL_PS")
      (libsource (lib "eagle-import") (part "pot-alps_POT_USVERTICAL_PS"))
    )
    (comp (ref "R43")
      (value "5.6k")
      (footprint "eagle-import:R0402")
      (libsource (lib "eagle-import") (part "R-US_R0402"))
    )
    (comp (ref "R44")
      (value "5.1k")
      (footprint "eagle-import:R0402")
      (libsource (lib "eagle-import") (part "R-US_R0402"))
    )
    (comp (ref "R45")
      (value "1.2k")
      (footprint "eagle-import:R0402")
      (libsource (lib "eagle-import") (part "R-US_R0402"))
    )
    (comp (ref "R46")
      (value "100k")
      (footprint "eagle-import:R0402")
      (libsource (lib "eagle-import") (part "R-US_R0402"))
    )
    (comp (ref "R47")
      (value "510")
      (footprint "eagle-import:R0402")
      (libsource (lib "eagle-import") (part "R-US_R0402"))
    )
    (comp (ref "R48")
      (value "5.1k")
      (footprint "eagle-import:R0402")
      (libsource (lib "eagle-import") (part "R-US_R0402"))
    )
    (comp (ref "R49")
      (value "5.1k")
      (footprint "eagle-import:R0402")
      (libsource (lib "eagle-import") (part "R-US_R0402"))
    )
    (comp (ref "R50")
      (value "5.1k")
      (footprint "eagle-import:R0402")
      (libsource (lib "eagle-import") (part "R-US_R0402"))
    )
    (comp (ref "R51")
      (value "100k")
      (footprint "eagle-import:R0402")
      (libsource (lib "eagle-import") (part "R-US_R0402"))
    )
    (comp (ref "R52")
      (value "1.0M")
      (footprint "eagle-import:R0402")
      (libsource (lib "eagle-import") (part "R-US_R0402"))
    )
    (comp (ref "R53")
      (value "510")
      (footprint "eagle-import:R0402")
      (libsource (lib "eagle-import") (part "R-US_R0402"))
    )
    (comp (ref "R54")
      (value "100k")
      (footprint "eagle-import:R0402")
      (libsource (lib "eagle-import") (part "R-US_R0402"))
    )
    (comp (ref "R55")
      (value "1.0M")
      (footprint "eagle-import:R0402")
      (libsource (lib "eagle-import") (part "R-US_R0402"))
    )
    (comp (ref "R56")
      (value "24k")
      (footprint "eagle-import:R0402")
      (libsource (lib "eagle-import") (part "R-US_R0402"))
    )
    (comp (ref "R57")
      (value "49.9k")
      (footprint "eagle-import:R0402")
      (libsource (lib "eagle-import") (part "R-US_R0402"))
    )
    (comp (ref "R58")
      (value "510")
      (footprint "eagle-import:R0402")
      (libsource (lib "eagle-import") (part "R-US_R0402"))
    )
    (comp (ref "R59")
      (value "20M")
      (footprint "eagle-import:R0402")
      (libsource (lib "eagle-import") (part "R-US_R0402"))
    )
    (comp (ref "C33")
      (value "560p")
      (footprint "eagle-import:C0402")
      (libsource (lib "eagle-import") (part "C-USC0402"))
    )
    (comp (ref "C34")
      (value "560p")
      (footprint "eagle-import:C0402")
      (libsource (lib "eagle-import") (part "C-USC0402"))
    )
    (comp (ref "C37")
      (value "100p")
      (footprint "eagle-import:C0402")
      (libsource (lib "eagle-import") (part "C-USC0402"))
    )
    (comp (ref "C38")
      (value "47p")
      (footprint "eagle-import:C0402")
      (libsource (lib "eagle-import") (part "C-USC0402"))
    )
    (comp (ref "C44")
      (value "47p")
      (footprint "eagle-import:C0402")
      (libsource (lib "eagle-import") (part "C-USC0402"))
    )
    (comp (ref "J10")
      (value "PJ301_THONKICONN6")
      (footprint "eagle-import:WQP_PJ_301M6")
      (libsource (lib "eagle-import") (part "PJ301_THONKICONN6"))
    )
    (comp (ref "J11")
      (value "PJ301_THONKICONN6")
      (footprint "eagle-import:WQP_PJ_301M6")
      (libsource (lib "eagle-import") (part "PJ301_THONKICONN6"))
    )
    (comp (ref "J12")
      (value "PJ301_THONKICONN6")
      (footprint "eagle-import:WQP_PJ_301M6")
      (libsource (lib "eagle-import") (part "PJ301_THONKICONN6"))
    )
    (comp (ref "LED4")
      (value "WP7113SRSGW")
      (footprint "eagle-import:LED5MM")
      (libsource (lib "eagle-import") (part "LED5MM"))
    )
    (comp (ref "R60")
      (value "20M")
      (footprint "eagle-import:R0402")
      (libsource (lib "eagle-import") (part "R-US_R0402"))
    )
    (comp (ref "R61")
      (value "510")
      (footprint "eagle-import:R0402")
      (libsource (lib "eagle-import") (part "R-US_R0402"))
    )
    (comp (ref "R62")
      (value "510")
      (footprint "eagle-import:R0402")
      (libsource (lib "eagle-import") (part "R-US_R0402"))
    )
    (comp (ref "R63")
      (value "49.9k")
      (footprint "eagle-import:R0402")
      (libsource (lib "eagle-import") (part "R-US_R0402"))
    )
    (comp (ref "R65")
      (value "510")
      (footprint "eagle-import:R0402")
      (libsource (lib "eagle-import") (part "R-US_R0402"))
    )
    (comp (ref "R66")
      (value "100k")
      (footprint "eagle-import:R0402")
      (libsource (lib "eagle-import") (part "R-US_R0402"))
    )
    (comp (ref "R67")
      (value "1.0M")
      (footprint "eagle-import:R0402")
      (libsource (lib "eagle-import") (part "R-US_R0402"))
    )
    (comp (ref "R68")
      (value "1.0M")
      (footprint "eagle-import:R0402")
      (libsource (lib "eagle-import") (part "R-US_R0402"))
    )
    (comp (ref "R69")
      (value "10kB")
      (footprint "eagle-import:ALPS_POT_VERTICAL")
      (libsource (lib "eagle-import") (part "POT_USVERTICAL"))
    )
    (comp (ref "R70")
      (value "10kB")
      (footprint "eagle-import:ALPS_POT_VERTICAL_PS")
      (libsource (lib "eagle-import") (part "pot-alps_POT_USVERTICAL_PS"))
    )
    (comp (ref "R71")
      (value "5.1k")
      (footprint "eagle-import:R0402")
      (libsource (lib "eagle-import") (part "R-US_R0402"))
    )
    (comp (ref "R72")
      (value "24k")
      (footprint "eagle-import:R0402")
      (libsource (lib "eagle-import") (part "R-US_R0402"))
    )
    (comp (ref "R73")
      (value "5.1k")
      (footprint "eagle-import:R0402")
      (libsource (lib "eagle-import") (part "R-US_R0402"))
    )
    (comp (ref "R75")
      (value "5.1k")
      (footprint "eagle-import:R0402")
      (libsource (lib "eagle-import") (part "R-US_R0402"))
    )
    (comp (ref "R76")
      (value "100k")
      (footprint "eagle-import:R0402")
      (libsource (lib "eagle-import") (part "R-US_R0402"))
    )
    (comp (ref "R77")
      (value "510")
      (footprint "eagle-import:R0402")
      (libsource (lib "eagle-import") (part "R-US_R0402"))
    )
    (comp (ref "R78")
      (value "1.2k")
      (footprint "eagle-import:R0402")
      (libsource (lib "eagle-import") (part "R-US_R0402"))
    )
    (comp (ref "R79")
      (value "100k")
      (footprint "eagle-import:R0402")
      (libsource (lib "eagle-import") (part "R-US_R0402"))
    )
  )
  (nets
    (net (code "1") (name "1_TO_2") (class "Default")
      (node (ref "IC1") (pin "14") (pinfunction "OUT_14") (pintype "output"))
      (node (ref "R30") (pin "2") (pinfunction "2_2") (pintype "passive"))
      (node (ref "R4") (pin "1") (pinfunction "1_1") (pintype "passive"))
    )
    (net (code "2") (name "2_TO_3") (class "Default")
      (node (ref "IC4") (pin "8") (pinfunction "OUT_8") (pintype "output"))
      (node (ref "R36") (pin "1") (pinfunction "1_1") (pintype "passive"))
      (node (ref "R48") (pin "2") (pinfunction "2_2") (pintype "passive"))
    )
    (net (code "3") (name "3_TO_4") (class "Default")
      (node (ref "IC5") (pin "14") (pinfunction "OUT_14") (pintype "output"))
      (node (ref "R43") (pin "1") (pinfunction "1_1") (pintype "passive"))
      (node (ref "R71") (pin "2") (pinfunction "2_2") (pintype "passive"))
    )
    (net (code "4") (name "AREF_+10") (class "Default")
      (node (ref "C16") (pin "1") (pinfunction "1_1") (pintype "passive"))
      (node (ref "C36") (pin "1") (pinfunction "1_1") (pintype "passive"))
      (node (ref "IC9") (pin "1") (pinfunction "C_1") (pintype "passive"))
      (node (ref "R16") (pin "2") (pinfunction "2_2") (pintype "passive"))
      (node (ref "R39") (pin "2") (pinfunction "2_2") (pintype "passive"))
      (node (ref "R56") (pin "2") (pinfunction "2_2") (pintype "passive"))
      (node (ref "R72") (pin "2") (pinfunction "2_2") (pintype "passive"))
      (node (ref "R74") (pin "2") (pinfunction "2_2") (pintype "passive"))
    )
    (net (code "5") (name "AREF_-2.5") (class "Default")
      (node (ref "C12") (pin "1") (pinfunction "1_1") (pintype "passive"))
      (node (ref "C32") (pin "1") (pinfunction "1_1") (pintype "passive"))
      (node (ref "IC8") (pin "2") (pinfunction "A_2") (pintype "passive"))
      (node (ref "R17") (pin "2") (pinfunction "2_2") (pintype "passive"))
      (node (ref "R19") (pin "2") (pinfunction "2_2") (pintype "passive"))
      (node (ref "R20") (pin "2") (pinfunction "2_2") (pintype "passive"))
      (node (ref "R23") (pin "2") (pinfunction "2_2") (pintype "passive"))
      (node (ref "R57") (pin "2") (pinfunction "2_2") (pintype "passive"))
      (node (ref "R59") (pin "2") (pinfunction "2_2") (pintype "passive"))
      (node (ref "R60") (pin "2") (pinfunction "2_2") (pintype "passive"))
      (node (ref "R63") (pin "2") (pinfunction "2_2") (pintype "passive"))
      (node (ref "R64") (pin "2") (pinfunction "2_2") (pintype "passive"))
    )
    (net (code "6") (name "GND") (class "Default")
      (node (ref "C1") (pin "+") (pinfunction "+_+") (pintype "passive"))
      (node (ref "C10") (pin "2") (pinfunction "2_2") (pintype "passive"))
      (node (ref "C11") (pin "1") (pinfunction "1_1") (pintype "passive"))
      (node (ref "C12") (pin "2") (pinfunction "2_2") (pintype "passive"))
      (node (ref "C13") (pin "2") (pinfunction "2_2") (pintype "passive"))
      (node (ref "C14") (pin "2") (pinfunction "2_2") (pintype "passive"))
      (node (ref "C15") (pin "1") (pinfunction "1_1") (pintype "passive"))
      (node (ref "C16") (pin "2") (pinfunction "2_2") (pintype "passive"))
      (node (ref "C19") (pin "2") (pinfunction "2_2") (pintype "passive"))
      (node (ref "C2") (pin "-") (pinfunction "-_-") (pintype "passive"))
      (node (ref "C20") (pin "1") (pinfunction "1_1") (pintype "passive"))
      (node (ref "C21") (pin "-") (pinfunction "-_-") (pintype "passive"))
      (node (ref "C22") (pin "+") (pinfunction "+_+") (pintype "passive"))
      (node (ref "C23") (pin "1") (pinfunction "1_1") (pintype "passive"))
      (node (ref "C24") (pin "2") (pinfunction "2_2") (pintype "passive"))
      (node (ref "C27") (pin "2") (pinfunction "2_2") (pintype "passive"))
      (node (ref "C28") (pin "2") (pinfunction "2_2") (pintype "passive"))
      (node (ref "C29") (pin "2") (pinfunction "2_2") (pintype "passive"))
      (node (ref "C3") (pin "1") (pinfunction "1_1") (pintype "passive"))
      (node (ref "C30") (pin "2") (pinfunction "2_2") (pintype "passive"))
      (node (ref "C31") (pin "1") (pinfunction "1_1") (pintype "passive"))
      (node (ref "C32") (pin "2") (pinfunction "2_2") (pintype "passive"))
      (node (ref "C33") (pin "2") (pinfunction "2_2") (pintype "passive"))
      (node (ref "C34") (pin "2") (pinfunction "2_2") (pintype "passive"))
      (node (ref "C35") (pin "1") (pinfunction "1_1") (pintype "passive"))
      (node (ref "C36") (pin "2") (pinfunction "2_2") (pintype "passive"))
      (node (ref "C39") (pin "1") (pinfunction "1_1") (pintype "passive"))
      (node (ref "C4") (pin "2") (pinfunction "2_2") (pintype "passive"))
      (node (ref "C40") (pin "2") (pinfunction "2_2") (pintype "passive"))
      (node (ref "C7") (pin "2") (pinfunction "2_2") (pintype "passive"))
      (node (ref "C8") (pin "2") (pinfunction "2_2") (pintype "passive"))
      (node (ref "C9") (pin "2") (pinfunction "2_2") (pintype "passive"))
      (node (ref "D1") (pin "C") (pinfunction "C_C") (pintype "passive"))
      (node (ref "IC1") (pin "10") (pinfunction "+IN_10") (pintype "input"))
      (node (ref "IC1") (pin "12") (pinfunction "+IN_12") (pintype "input"))
      (node (ref "IC1") (pin "3") (pinfunction "+IN_3") (pintype "input"))
      (node (ref "IC1") (pin "5") (pinfunction "+IN_5") (pintype "input"))
      (node (ref "IC10") (pin "10") (pinfunction "+IN_10") (pintype "input"))
      (node (ref "IC10") (pin "12") (pinfunction "+IN_12") (pintype "input"))
      (node (ref "IC10") (pin "3") (pinfunction "+IN_3") (pintype "input"))
      (node (ref "IC10") (pin "5") (pinfunction "+IN_5") (pintype "input"))
      (node (ref "IC3") (pin "8") (pinfunction "GND_8") (pintype "power_in"))
      (node (ref "IC4") (pin "10") (pinfunction "+IN_10") (pintype "input"))
      (node (ref "IC4") (pin "12") (pinfunction "+IN_12") (pintype "input"))
      (node (ref "IC4") (pin "3") (pinfunction "+IN_3") (pintype "input"))
      (node (ref "IC4") (pin "5") (pinfunction "+IN_5") (pintype "input"))
      (node (ref "IC5") (pin "10") (pinfunction "+IN_10") (pintype "input"))
      (node (ref "IC5") (pin "12") (pinfunction "+IN_12") (pintype "input"))
      (node (ref "IC5") (pin "3") (pinfunction "+IN_3") (pintype "input"))
      (node (ref "IC5") (pin "5") (pinfunction "+IN_5") (pintype "input"))
      (node (ref "IC7") (pin "8") (pinfunction "GND_8") (pintype "power_in"))
      (node (ref "IC8") (pin "1") (pinfunction "C_1") (pintype "passive"))
      (node (ref "IC9") (pin "2") (pinfunction "A_2") (pintype "passive"))
      (node (ref "J1") (pin "P1") (pinfunction "1_P1") (pintype "passive"))
      (node (ref "J1") (pin "P2") (pinfunction "2_P2") (pintype "passive"))
      (node (ref "J10") (pin "P1") (pinfunction "1_P1") (pintype "passive"))
      (node (ref "J10") (pin "P2") (pinfunction "2_P2") (pintype "passive"))
      (node (ref "J11") (pin "P1") (pinfunction "1_P1") (pintype "passive"))
      (node (ref "J12") (pin "P1") (pinfunction "1_P1") (pintype "passive"))
      (node (ref "J2") (pin "P1") (pinfunction "1_P1") (pintype "passive"))
      (node (ref "J3") (pin "P1") (pinfunction "1_P1") (pintype "passive"))
      (node (ref "J4") (pin "P1") (pinfunction "1_P1") (pintype "passive"))
      (node (ref "J4") (pin "P2") (pinfunction "2_P2") (pintype "passive"))
      (node (ref "J5") (pin "P1") (pinfunction "1_P1") (pintype "passive"))
      (node (ref "J6") (pin "P1") (pinfunction "1_P1") (pintype "passive"))
      (node (ref "J7") (pin "P1") (pinfunction "1_P1") (pintype "passive"))
      (node (ref "J7") (pin "P2") (pinfunction "2_P2") (pintype "passive"))
      (node (ref "J8") (pin "P1") (pinfunction "1_P1") (pintype "passive"))
      (node (ref "J9") (pin "P1") (pinfunction "1_P1") (pintype "passive"))
      (node (ref "JP5") (pin "3") (pinfunction "3_3") (pintype "passive"))
      (node (ref "JP5") (pin "4") (pinfunction "4_4") (pintype "passive"))
      (node (ref "JP5") (pin "5") (pinfunction "5_5") (pintype "passive"))
      (node (ref "JP5") (pin "6") (pinfunction "6_6") (pintype "passive"))
      (node (ref "JP5") (pin "7") (pinfunction "7_7") (pintype "passive"))
      (node (ref "JP5") (pin "8") (pinfunction "8_8") (pintype "passive"))
      (node (ref "R15") (pin "1") (pinfunction "1_1") (pintype "passive"))
      (node (ref "R27") (pin "1") (pinfunction "1_1") (pintype "passive"))
      (node (ref "R29") (pin "P$3") (pinfunction "A_P$3") (pintype "passive"))
      (node (ref "R3") (pin "P$3") (pinfunction "A_P$3") (pintype "passive"))
      (node (ref "R35") (pin "1") (pinfunction "1_1") (pintype "passive"))
      (node (ref "R38") (pin "2") (pinfunction "2_2") (pintype "passive"))
      (node (ref "R42") (pin "P$3") (pinfunction "A_P$3") (pintype "passive"))
      (node (ref "R45") (pin "2") (pinfunction "2_2") (pintype "passive"))
      (node (ref "R47") (pin "1") (pinfunction "1_1") (pintype "passive"))
      (node (ref "R55") (pin "1") (pinfunction "1_1") (pintype "passive"))
      (node (ref "R6") (pin "2") (pinfunction "2_2") (pintype "passive"))
      (node (ref "R68") (pin "1") (pinfunction "1_1") (pintype "passive"))
      (node (ref "R70") (pin "P$3") (pinfunction "A_P$3") (pintype "passive"))
      (node (ref "R77") (pin "1") (pinfunction "1_1") (pintype "passive"))
      (node (ref "R78") (pin "2") (pinfunction "2_2") (pintype "passive"))
      (node (ref "R8") (pin "1") (pinfunction "1_1") (pintype "passive"))
    )
    (net (code "7") (name "Net-(C9-Pad1)") (class "Default")
      (node (ref "C9") (pin "1") (pinfunction "1_1") (pintype "passive"))
      (node (ref "R13") (pin "1") (pinfunction "1_1") (pintype "passive"))
    )
    (net (code "8") (name "Net-(C10-Pad1)") (class "Default")
      (node (ref "C10") (pin "1") (pinfunction "1_1") (pintype "passive"))
      (node (ref "R18") (pin "1") (pinfunction "1_1") (pintype "passive"))
    )
    (net (code "9") (name "Net-(C13-Pad1)") (class "Default")
      (node (ref "C13") (pin "1") (pinfunction "1_1") (pintype "passive"))
      (node (ref "R21") (pin "1") (pinfunction "1_1") (pintype "passive"))
    )
    (net (code "10") (name "Net-(C14-Pad1)") (class "Default")
      (node (ref "C14") (pin "1") (pinfunction "1_1") (pintype "passive"))
      (node (ref "R24") (pin "1") (pinfunction "1_1") (pintype "passive"))
    )
    (net (code "11") (name "Net-(C29-Pad1)") (class "Default")
      (node (ref "C29") (pin "1") (pinfunction "1_1") (pintype "passive"))
      (node (ref "R53") (pin "1") (pinfunction "1_1") (pintype "passive"))
    )
    (net (code "12") (name "Net-(C30-Pad1)") (class "Default")
      (node (ref "C30") (pin "1") (pinfunction "1_1") (pintype "passive"))
      (node (ref "R58") (pin "1") (pinfunction "1_1") (pintype "passive"))
    )
    (net (code "13") (name "Net-(C33-Pad1)") (class "Default")
      (node (ref "C33") (pin "1") (pinfunction "1_1") (pintype "passive"))
      (node (ref "R61") (pin "1") (pinfunction "1_1") (pintype "passive"))
    )
    (net (code "14") (name "Net-(C34-Pad1)") (class "Default")
      (node (ref "C34") (pin "1") (pinfunction "1_1") (pintype "passive"))
      (node (ref "R65") (pin "1") (pinfunction "1_1") (pintype "passive"))
    )
    (net (code "15") (name "Net-(D2-PadA)") (class "Default")
      (node (ref "D2") (pin "A") (pinfunction "A_A") (pintype "passive"))
      (node (ref "JP5") (pin "1") (pinfunction "1_1") (pintype "passive"))
      (node (ref "JP5") (pin "2") (pinfunction "2_2") (pintype "passive"))
    )
    (net (code "16") (name "Net-(D2-PadC)") (class "Default")
      (node (ref "D2") (pin "C") (pinfunction "C_C") (pintype "passive"))
      (node (ref "L2") (pin "2") (pinfunction "2_2") (pintype "passive"))
    )
    (net (code "17") (name "Net-(IC1A--IN)") (class "Default")
      (node (ref "C5") (pin "1") (pinfunction "1_1") (pintype "passive"))
      (node (ref "IC1") (pin "2") (pinfunction "-IN_2") (pintype "input"))
      (node (ref "IC3") (pin "4") (pinfunction "OUT_4") (pintype "output"))
      (node (ref "R19") (pin "1") (pinfunction "1_1") (pintype "passive"))
      (node (ref "R3") (pin "P$1") (pinfunction "E_P$1") (pintype "passive"))
    )
    (net (code "18") (name "Net-(IC1A-OUT)") (class "Default")
      (node (ref "C5") (pin "2") (pinfunction "2_2") (pintype "passive"))
      (node (ref "IC1") (pin "1") (pinfunction "OUT_1") (pintype "output"))
      (node (ref "IC3") (pin "14") (pinfunction "CTRL_14") (pintype "input"))
      (node (ref "R1") (pin "P$1") (pinfunction "E_P$1") (pintype "passive"))
    )
    (net (code "19") (name "Net-(IC1B--IN)") (class "Default")
      (node (ref "C41") (pin "1") (pinfunction "1_1") (pintype "passive"))
      (node (ref "IC1") (pin "6") (pinfunction "-IN_6") (pintype "input"))
      (node (ref "IC3") (pin "13") (pinfunction "OUT_13") (pintype "output"))
      (node (ref "R7") (pin "2") (pinfunction "2_2") (pintype "passive"))
    )
    (net (code "20") (name "Net-(IC1B-OUT)") (class "Default")
      (node (ref "C41") (pin "2") (pinfunction "2_2") (pintype "passive"))
      (node (ref "IC1") (pin "7") (pinfunction "OUT_7") (pintype "output"))
      (node (ref "R7") (pin "1") (pinfunction "1_1") (pintype "passive"))
      (node (ref "R9") (pin "2") (pinfunction "2_2") (pintype "passive"))
    )
    (net (code "21") (name "Net-(IC1C--IN)") (class "Default")
      (node (ref "C6") (pin "1") (pinfunction "1_1") (pintype "passive"))
      (node (ref "IC1") (pin "9") (pinfunction "-IN_9") (pintype "input"))
      (node (ref "R10") (pin "2") (pinfunction "2_2") (pintype "passive"))
      (node (ref "R9") (pin "1") (pinfunction "1_1") (pintype "passive"))
    )
    (net (code "22") (name "Net-(IC1C-OUT)") (class "Default")
      (node (ref "C6") (pin "2") (pinfunction "2_2") (pintype "passive"))
      (node (ref "IC1") (pin "8") (pinfunction "OUT_8") (pintype "output"))
      (node (ref "R10") (pin "1") (pinfunction "1_1") (pintype "passive"))
      (node (ref "R12") (pin "1") (pinfunction "1_1") (pintype "passive"))
      (node (ref "R2") (pin "2") (pinfunction "2_2") (pintype "passive"))
    )
    (net (code "23") (name "Net-(IC1D--IN)") (class "Default")
      (node (ref "IC1") (pin "13") (pinfunction "-IN_13") (pintype "input"))
      (node (ref "R4") (pin "2") (pinfunction "2_2") (pintype "passive"))
      (node (ref "R5") (pin "1") (pinfunction "1_1") (pintype "passive"))
    )
    (net (code "24") (name "Net-(IC2A-+IN)") (class "Default")
      (node (ref "IC2") (pin "3") (pinfunction "+IN_3") (pintype "input"))
      (node (ref "R12") (pin "2") (pinfunction "2_2") (pintype "passive"))
      (node (ref "R15") (pin "2") (pinfunction "2_2") (pintype "passive"))
    )
    (net (code "25") (name "Net-(IC2A--IN)") (class "Default")
      (node (ref "IC2") (pin "2") (pinfunction "-IN_2") (pintype "input"))
      (node (ref "LED1") (pin "A") (pinfunction "A_A") (pintype "passive"))
      (node (ref "R6") (pin "1") (pinfunction "1_1") (pintype "passive"))
    )
    (net (code "26") (name "Net-(IC2A-OUT)") (class "Default")
      (node (ref "IC2") (pin "1") (pinfunction "OUT_1") (pintype "output"))
      (node (ref "LED1") (pin "K") (pinfunction "C_K") (pintype "passive"))
    )
    (net (code "27") (name "Net-(IC2B-+IN)") (class "Default")
      (node (ref "IC2") (pin "5") (pinfunction "+IN_5") (pintype "input"))
      (node (ref "R26") (pin "2") (pinfunction "2_2") (pintype "passive"))
      (node (ref "R27") (pin "2") (pinfunction "2_2") (pintype "passive"))
    )
    (net (code "28") (name "Net-(IC2B--IN)") (class "Default")
      (node (ref "IC2") (pin "6") (pinfunction "-IN_6") (pintype "input"))
      (node (ref "LED2") (pin "A") (pinfunction "A_A") (pintype "passive"))
      (node (ref "R38") (pin "1") (pinfunction "1_1") (pintype "passive"))
    )
    (net (code "29") (name "Net-(IC2B-OUT)") (class "Default")
      (node (ref "IC2") (pin "7") (pinfunction "OUT_7") (pintype "output"))
      (node (ref "LED2") (pin "K") (pinfunction "C_K") (pintype "passive"))
    )
    (net (code "30") (name "Net-(IC3A-CTRL)") (class "Default")
      (node (ref "IC3") (pin "3") (pinfunction "CTRL_3") (pintype "input"))
      (node (ref "R1") (pin "P$2") (pinfunction "S_P$2") (pintype "passive"))
    )
    (net (code "31") (name "Net-(IC3A-IN)") (class "Default")
      (node (ref "IC3") (pin "2") (pinfunction "IN_2") (pintype "input"))
      (node (ref "R13") (pin "2") (pinfunction "2_2") (pintype "passive"))
      (node (ref "R17") (pin "1") (pinfunction "1_1") (pintype "passive"))
    )
    (net (code "32") (name "Net-(IC3B-CTRL)") (class "Default")
      (node (ref "IC3") (pin "6") (pinfunction "CTRL_6") (pintype "input"))
      (node (ref "R28") (pin "P$2") (pinfunction "S_P$2") (pintype "passive"))
    )
    (net (code "33") (name "Net-(IC3B-IN)") (class "Default")
      (node (ref "IC3") (pin "7") (pinfunction "IN_7") (pintype "input"))
      (node (ref "R23") (pin "1") (pinfunction "1_1") (pintype "passive"))
      (node (ref "R24") (pin "2") (pinfunction "2_2") (pintype "passive"))
    )
    (net (code "34") (name "Net-(IC3B-OUT)") (class "Default")
      (node (ref "C18") (pin "1") (pinfunction "1_1") (pintype "passive"))
      (node (ref "IC3") (pin "5") (pinfunction "OUT_5") (pintype "output"))
      (node (ref "IC4") (pin "6") (pinfunction "-IN_6") (pintype "input"))
      (node (ref "R20") (pin "1") (pinfunction "1_1") (pintype "passive"))
      (node (ref "R29") (pin "P$1") (pinfunction "E_P$1") (pintype "passive"))
    )
    (net (code "35") (name "Net-(IC3C-CTRL)") (class "Default")
      (node (ref "C18") (pin "2") (pinfunction "2_2") (pintype "passive"))
      (node (ref "IC3") (pin "11") (pinfunction "CTRL_11") (pintype "input"))
      (node (ref "IC4") (pin "7") (pinfunction "OUT_7") (pintype "output"))
      (node (ref "R28") (pin "P$1") (pinfunction "E_P$1") (pintype "passive"))
    )
    (net (code "36") (name "Net-(IC3C-IN)") (class "Default")
      (node (ref "IC3") (pin "10") (pinfunction "IN_10") (pintype "input"))
      (node (ref "R21") (pin "2") (pinfunction "2_2") (pintype "passive"))
      (node (ref "R25") (pin "1") (pinfunction "1_1") (pintype "passive"))
    )
    (net (code "37") (name "Net-(IC3C-OUT)") (class "Default")
      (node (ref "C42") (pin "1") (pinfunction "1_1") (pintype "passive"))
      (node (ref "IC3") (pin "12") (pinfunction "OUT_12") (pintype "output"))
      (node (ref "IC4") (pin "2") (pinfunction "-IN_2") (pintype "input"))
      (node (ref "R33") (pin "2") (pinfunction "2_2") (pintype "passive"))
    )
    (net (code "38") (name "Net-(IC3D-IN)") (class "Default")
      (node (ref "IC3") (pin "15") (pinfunction "IN_15") (pintype "input"))
      (node (ref "R14") (pin "1") (pinfunction "1_1") (pintype "passive"))
      (node (ref "R18") (pin "2") (pinfunction "2_2") (pintype "passive"))
    )
    (net (code "39") (name "Net-(IC4A-OUT)") (class "Default")
      (node (ref "C42") (pin "2") (pinfunction "2_2") (pintype "passive"))
      (node (ref "IC4") (pin "1") (pinfunction "OUT_1") (pintype "output"))
      (node (ref "R32") (pin "2") (pinfunction "2_2") (pintype "passive"))
      (node (ref "R33") (pin "1") (pinfunction "1_1") (pintype "passive"))
    )
    (net (code "40") (name "Net-(IC4C--IN)") (class "Default")
      (node (ref "IC4") (pin "9") (pinfunction "-IN_9") (pintype "input"))
      (node (ref "R34") (pin "1") (pinfunction "1_1") (pintype "passive"))
      (node (ref "R36") (pin "2") (pinfunction "2_2") (pintype "passive"))
    )
    (net (code "41") (name "Net-(IC4D--IN)") (class "Default")
      (node (ref "C17") (pin "1") (pinfunction "1_1") (pintype "passive"))
      (node (ref "IC4") (pin "13") (pinfunction "-IN_13") (pintype "input"))
      (node (ref "R30") (pin "1") (pinfunction "1_1") (pintype "passive"))
      (node (ref "R31") (pin "2") (pinfunction "2_2") (pintype "passive"))
      (node (ref "R32") (pin "1") (pinfunction "1_1") (pintype "passive"))
    )
    (net (code "42") (name "Net-(IC4D-OUT)") (class "Default")
      (node (ref "C17") (pin "2") (pinfunction "2_2") (pintype "passive"))
      (node (ref "IC4") (pin "14") (pinfunction "OUT_14") (pintype "output"))
      (node (ref "R22") (pin "2") (pinfunction "2_2") (pintype "passive"))
      (node (ref "R26") (pin "1") (pinfunction "1_1") (pintype "passive"))
      (node (ref "R31") (pin "1") (pinfunction "1_1") (pintype "passive"))
    )
    (net (code "43") (name "Net-(IC5A--IN)") (class "Default")
      (node (ref "C25") (pin "1") (pinfunction "1_1") (pintype "passive"))
      (node (ref "IC5") (pin "2") (pinfunction "-IN_2") (pintype "input"))
      (node (ref "IC7") (pin "4") (pinfunction "OUT_4") (pintype "output"))
      (node (ref "R42") (pin "P$1") (pinfunction "E_P$1") (pintype "passive"))
      (node (ref "R59") (pin "1") (pinfunction "1_1") (pintype "passive"))
    )
    (net (code "44") (name "Net-(IC5A-OUT)") (class "Default")
      (node (ref "C25") (pin "2") (pinfunction "2_2") (pintype "passive"))
      (node (ref "IC5") (pin "1") (pinfunction "OUT_1") (pintype "output"))
      (node (ref "IC7") (pin "14") (pinfunction "CTRL_14") (pintype "input"))
      (node (ref "R40") (pin "P$1") (pinfunction "E_P$1") (pintype "passive"))
    )
    (net (code "45") (name "Net-(IC5B--IN)") (class "Default")
      (node (ref "C43") (pin "1") (pinfunction "1_1") (pintype "passive"))
      (node (ref "IC5") (pin "6") (pinfunction "-IN_6") (pintype "input"))
      (node (ref "IC7") (pin "13") (pinfunction "OUT_13") (pintype "output"))
      (node (ref "R46") (pin "2") (pinfunction "2_2") (pintype "passive"))
    )
    (net (code "46") (name "Net-(IC5B-OUT)") (class "Default")
      (node (ref "C43") (pin "2") (pinfunction "2_2") (pintype "passive"))
      (node (ref "IC5") (pin "7") (pinfunction "OUT_7") (pintype "output"))
      (node (ref "R46") (pin "1") (pinfunction "1_1") (pintype "passive"))
      (node (ref "R49") (pin "2") (pinfunction "2_2") (pintype "passive"))
    )
    (net (code "47") (name "Net-(IC5C--IN)") (class "Default")
      (node (ref "C26") (pin "1") (pinfunction "1_1") (pintype "passive"))
      (node (ref "IC5") (pin "9") (pinfunction "-IN_9") (pintype "input"))
      (node (ref "R48") (pin "1") (pinfunction "1_1") (pintype "passive"))
      (node (ref "R49") (pin "1") (pinfunction "1_1") (pintype "passive"))
      (node (ref "R50") (pin "2") (pinfunction "2_2") (pintype "passive"))
    )
    (net (code "48") (name "Net-(IC5C-OUT)") (class "Default")
      (node (ref "C26") (pin "2") (pinfunction "2_2") (pintype "passive"))
      (node (ref "IC5") (pin "8") (pinfunction "OUT_8") (pintype "output"))
      (node (ref "R41") (pin "2") (pinfunction "2_2") (pintype "passive"))
      (node (ref "R50") (pin "1") (pinfunction "1_1") (pintype "passive"))
      (node (ref "R52") (pin "1") (pinfunction "1_1") (pintype "passive"))
    )
    (net (code "49") (name "Net-(IC5D--IN)") (class "Default")
      (node (ref "IC5") (pin "13") (pinfunction "-IN_13") (pintype "input"))
      (node (ref "R43") (pin "2") (pinfunction "2_2") (pintype "passive"))
      (node (ref "R44") (pin "1") (pinfunction "1_1") (pintype "passive"))
    )
    (net (code "50") (name "Net-(IC6A-+IN)") (class "Default")
      (node (ref "IC6") (pin "3") (pinfunction "+IN_3") (pintype "input"))
      (node (ref "R52") (pin "2") (pinfunction "2_2") (pintype "passive"))
      (node (ref "R55") (pin "2") (pinfunction "2_2") (pintype "passive"))
    )
    (net (code "51") (name "Net-(IC6A--IN)") (class "Default")
      (node (ref "IC6") (pin "2") (pinfunction "-IN_2") (pintype "input"))
      (node (ref "LED3") (pin "A") (pinfunction "A_A") (pintype "passive"))
      (node (ref "R45") (pin "1") (pinfunction "1_1") (pintype "passive"))
    )
    (net (code "52") (name "Net-(IC6A-OUT)") (class "Default")
      (node (ref "IC6") (pin "1") (pinfunction "OUT_1") (pintype "output"))
      (node (ref "LED3") (pin "K") (pinfunction "C_K") (pintype "passive"))
    )
    (net (code "53") (name "Net-(IC6B-+IN)") (class "Default")
      (node (ref "IC6") (pin "5") (pinfunction "+IN_5") (pintype "input"))
      (node (ref "R67") (pin "2") (pinfunction "2_2") (pintype "passive"))
      (node (ref "R68") (pin "2") (pinfunction "2_2") (pintype "passive"))
    )
    (net (code "54") (name "Net-(IC6B--IN)") (class "Default")
      (node (ref "IC6") (pin "6") (pinfunction "-IN_6") (pintype "input"))
      (node (ref "LED4") (pin "A") (pinfunction "A_A") (pintype "passive"))
      (node (ref "R78") (pin "1") (pinfunction "1_1") (pintype "passive"))
    )
    (net (code "55") (name "Net-(IC6B-OUT)") (class "Default")
      (node (ref "IC6") (pin "7") (pinfunction "OUT_7") (pintype "output"))
      (node (ref "LED4") (pin "K") (pinfunction "C_K") (pintype "passive"))
    )
    (net (code "56") (name "Net-(IC7A-CTRL)") (class "Default")
      (node (ref "IC7") (pin "3") (pinfunction "CTRL_3") (pintype "input"))
      (node (ref "R40") (pin "P$2") (pinfunction "S_P$2") (pintype "passive"))
    )
    (net (code "57") (name "Net-(IC7A-IN)") (class "Default")
      (node (ref "IC7") (pin "2") (pinfunction "IN_2") (pintype "input"))
      (node (ref "R53") (pin "2") (pinfunction "2_2") (pintype "passive"))
      (node (ref "R57") (pin "1") (pinfunction "1_1") (pintype "passive"))
    )
    (net (code "58") (name "Net-(IC7B-CTRL)") (class "Default")
      (node (ref "IC7") (pin "6") (pinfunction "CTRL_6") (pintype "input"))
      (node (ref "R69") (pin "P$2") (pinfunction "S_P$2") (pintype "passive"))
    )
    (net (code "59") (name "Net-(IC7B-IN)") (class "Default")
      (node (ref "IC7") (pin "7") (pinfunction "IN_7") (pintype "input"))
      (node (ref "R63") (pin "1") (pinfunction "1_1") (pintype "passive"))
      (node (ref "R65") (pin "2") (pinfunction "2_2") (pintype "passive"))
    )
    (net (code "60") (name "Net-(IC7C-IN)") (class "Default")
      (node (ref "IC7") (pin "10") (pinfunction "IN_10") (pintype "input"))
      (node (ref "R61") (pin "2") (pinfunction "2_2") (pintype "passive"))
      (node (ref "R66") (pin "1") (pinfunction "1_1") (pintype "passive"))
    )
    (net (code "61") (name "Net-(IC7D-IN)") (class "Default")
      (node (ref "IC7") (pin "15") (pinfunction "IN_15") (pintype "input"))
      (node (ref "R54") (pin "1") (pinfunction "1_1") (pintype "passive"))
      (node (ref "R58") (pin "2") (pinfunction "2_2") (pintype "passive"))
    )
    (net (code "62") (name "Net-(IC10A--IN)") (class "Default")
      (node (ref "C44") (pin "1") (pinfunction "1_1") (pintype "passive"))
      (node (ref "IC10") (pin "2") (pinfunction "-IN_2") (pintype "input"))
      (node (ref "IC7") (pin "12") (pinfunction "OUT_12") (pintype "output"))
      (node (ref "R76") (pin "2") (pinfunction "2_2") (pintype "passive"))
    )
    (net (code "63") (name "Net-(IC10A-OUT)") (class "Default")
      (node (ref "C44") (pin "2") (pinfunction "2_2") (pintype "passive"))
      (node (ref "IC10") (pin "1") (pinfunction "OUT_1") (pintype "output"))
      (node (ref "R75") (pin "2") (pinfunction "2_2") (pintype "passive"))
      (node (ref "R76") (pin "1") (pinfunction "1_1") (pintype "passive"))
    )
    (net (code "64") (name "Net-(IC10B--IN)") (class "Default")
      (node (ref "C38") (pin "1") (pinfunction "1_1") (pintype "passive"))
      (node (ref "IC10") (pin "6") (pinfunction "-IN_6") (pintype "input"))
      (node (ref "IC7") (pin "5") (pinfunction "OUT_5") (pintype "output"))
      (node (ref "R60") (pin "1") (pinfunction "1_1") (pintype "passive"))
      (node (ref "R70") (pin "P$1") (pinfunction "E_P$1") (pintype "passive"))
    )
    (net (code "65") (name "Net-(IC10B-OUT)") (class "Default")
      (node (ref "C38") (pin "2") (pinfunction "2_2") (pintype "passive"))
      (node (ref "IC10") (pin "7") (pinfunction "OUT_7") (pintype "output"))
      (node (ref "IC7") (pin "11") (pinfunction "CTRL_11") (pintype "input"))
      (node (ref "R69") (pin "P$1") (pinfunction "E_P$1") (pintype "passive"))
    )
    (net (code "66") (name "Net-(IC10C--IN)") (class "Default")
      (node (ref "IC10") (pin "8") (pinfunction "OUT_8") (pintype "output"))
      (node (ref "IC10") (pin "9") (pinfunction "-IN_9") (pintype "input"))
    )
    (net (code "67") (name "Net-(IC10D--IN)") (class "Default")
      (node (ref "C37") (pin "1") (pinfunction "1_1") (pintype "passive"))
      (node (ref "IC10") (pin "13") (pinfunction "-IN_13") (pintype "input"))
      (node (ref "R71") (pin "1") (pinfunction "1_1") (pintype "passive"))
      (node (ref "R73") (pin "2") (pinfunction "2_2") (pintype "passive"))
      (node (ref "R75") (pin "1") (pinfunction "1_1") (pintype "passive"))
    )
    (net (code "68") (name "Net-(IC10D-OUT)") (class "Default")
      (node (ref "C37") (pin "2") (pinfunction "2_2") (pintype "passive"))
      (node (ref "IC10") (pin "14") (pinfunction "OUT_14") (pintype "output"))
      (node (ref "R62") (pin "2") (pinfunction "2_2") (pintype "passive"))
      (node (ref "R67") (pin "1") (pinfunction "1_1") (pintype "passive"))
      (node (ref "R73") (pin "1") (pinfunction "1_1") (pintype "passive"))
    )
    (net (code "69") (name "Net-(J1-3)") (class "Default")
      (node (ref "J1") (pin "P3") (pinfunction "3_P3") (pintype "passive"))
      (node (ref "R14") (pin "2") (pinfunction "2_2") (pintype "passive"))
    )
    (net (code "70") (name "Net-(J2-2)") (class "Default")
      (node (ref "J2") (pin "P2") (pinfunction "2_P2") (pintype "passive"))
      (node (ref "R5") (pin "2") (pinfunction "2_2") (pintype "passive"))
    )
    (net (code "71") (name "Net-(J2-3)") (class "Default")
      (node (ref "J2") (pin "P3") (pinfunction "3_P3") (pintype "passive"))
      (node (ref "R2") (pin "1") (pinfunction "1_1") (pintype "passive"))
    )
    (net (code "72") (name "Net-(J3-2)") (class "Default")
      (node (ref "J3") (pin "P2") (pinfunction "2_P2") (pintype "passive"))
      (node (ref "R16") (pin "1") (pinfunction "1_1") (pintype "passive"))
    )
    (net (code "73") (name "Net-(J3-3)") (class "Default")
      (node (ref "J3") (pin "P3") (pinfunction "3_P3") (pintype "passive"))
      (node (ref "R11") (pin "2") (pinfunction "2_2") (pintype "passive"))
    )
    (net (code "74") (name "Net-(J4-3)") (class "Default")
      (node (ref "J4") (pin "P3") (pinfunction "3_P3") (pintype "passive"))
      (node (ref "R25") (pin "2") (pinfunction "2_2") (pintype "passive"))
    )
    (net (code "75") (name "Net-(J5-2)") (class "Default")
      (node (ref "J5") (pin "P2") (pinfunction "2_P2") (pintype "passive"))
      (node (ref "R34") (pin "2") (pinfunction "2_2") (pintype "passive"))
    )
    (net (code "76") (name "Net-(J5-3)") (class "Default")
      (node (ref "J5") (pin "P3") (pinfunction "3_P3") (pintype "passive"))
      (node (ref "R22") (pin "1") (pinfunction "1_1") (pintype "passive"))
    )
    (net (code "77") (name "Net-(J6-2)") (class "Default")
      (node (ref "J6") (pin "P2") (pinfunction "2_P2") (pintype "passive"))
      (node (ref "R39") (pin "1") (pinfunction "1_1") (pintype "passive"))
    )
    (net (code "78") (name "Net-(J6-3)") (class "Default")
      (node (ref "J6") (pin "P3") (pinfunction "3_P3") (pintype "passive"))
      (node (ref "R37") (pin "2") (pinfunction "2_2") (pintype "passive"))
    )
    (net (code "79") (name "Net-(J7-3)") (class "Default")
      (node (ref "J7") (pin "P3") (pinfunction "3_P3") (pintype "passive"))
      (node (ref "R54") (pin "2") (pinfunction "2_2") (pintype "passive"))
    )
    (net (code "80") (name "Net-(J8-2)") (class "Default")
      (node (ref "J8") (pin "P2") (pinfunction "2_P2") (pintype "passive"))
      (node (ref "R44") (pin "2") (pinfunction "2_2") (pintype "passive"))
    )
    (net (code "81") (name "Net-(J8-3)") (class "Default")
      (node (ref "J8") (pin "P3") (pinfunction "3_P3") (pintype "passive"))
      (node (ref "R41") (pin "1") (pinfunction "1_1") (pintype "passive"))
    )
    (net (code "82") (name "Net-(J9-2)") (class "Default")
      (node (ref "J9") (pin "P2") (pinfunction "2_P2") (pintype "passive"))
      (node (ref "R56") (pin "1") (pinfunction "1_1") (pintype "passive"))
    )
    (net (code "83") (name "Net-(J9-3)") (class "Default")
      (node (ref "J9") (pin "P3") (pinfunction "3_P3") (pintype "passive"))
      (node (ref "R51") (pin "2") (pinfunction "2_2") (pintype "passive"))
    )
    (net (code "84") (name "Net-(J10-3)") (class "Default")
      (node (ref "J10") (pin "P3") (pinfunction "3_P3") (pintype "passive"))
      (node (ref "R66") (pin "2") (pinfunction "2_2") (pintype "passive"))
    )
    (net (code "85") (name "Net-(J11-3)") (class "Default")
      (node (ref "J11") (pin "P3") (pinfunction "3_P3") (pintype "passive"))
      (node (ref "R62") (pin "1") (pinfunction "1_1") (pintype "passive"))
    )
    (net (code "86") (name "Net-(J12-2)") (class "Default")
      (node (ref "J12") (pin "P2") (pinfunction "2_P2") (pintype "passive"))
      (node (ref "R72") (pin "1") (pinfunction "1_1") (pintype "passive"))
    )
    (net (code "87") (name "Net-(J12-3)") (class "Default")
      (node (ref "J12") (pin "P3") (pinfunction "3_P3") (pintype "passive"))
      (node (ref "R79") (pin "2") (pinfunction "2_2") (pintype "passive"))
    )
    (net (code "88") (name "Net-(JP5-Pad10)") (class "Default")
      (node (ref "JP5") (pin "10") (pinfunction "10_10") (pintype "passive"))
      (node (ref "JP5") (pin "9") (pinfunction "9_9") (pintype "passive"))
      (node (ref "P1") (pin "2") (pinfunction "2_2") (pintype "bidirectional"))
    )
    (net (code "89") (name "Net-(L1-Pad2)") (class "Default")
      (node (ref "L1") (pin "2") (pinfunction "2_2") (pintype "passive"))
      (node (ref "P1") (pin "1") (pinfunction "1_1") (pintype "bidirectional"))
    )
    (net (code "90") (name "Net-(R1-A)") (class "Default")
      (node (ref "R1") (pin "P$3") (pinfunction "A_P$3") (pintype "passive"))
      (node (ref "R8") (pin "2") (pinfunction "2_2") (pintype "passive"))
    )
    (net (code "91") (name "Net-(R3-S)") (class "Default")
      (node (ref "R11") (pin "1") (pinfunction "1_1") (pintype "passive"))
      (node (ref "R3") (pin "P$2") (pinfunction "S_P$2") (pintype "passive"))
    )
    (net (code "92") (name "Net-(R28-A)") (class "Default")
      (node (ref "R28") (pin "P$3") (pinfunction "A_P$3") (pintype "passive"))
      (node (ref "R35") (pin "2") (pinfunction "2_2") (pintype "passive"))
    )
    (net (code "93") (name "Net-(R29-S)") (class "Default")
      (node (ref "R29") (pin "P$2") (pinfunction "S_P$2") (pintype "passive"))
      (node (ref "R37") (pin "1") (pinfunction "1_1") (pintype "passive"))
    )
    (net (code "94") (name "Net-(R40-A)") (class "Default")
      (node (ref "R40") (pin "P$3") (pinfunction "A_P$3") (pintype "passive"))
      (node (ref "R47") (pin "2") (pinfunction "2_2") (pintype "passive"))
    )
    (net (code "95") (name "Net-(R42-S)") (class "Default")
      (node (ref "R42") (pin "P$2") (pinfunction "S_P$2") (pintype "passive"))
      (node (ref "R51") (pin "1") (pinfunction "1_1") (pintype "passive"))
    )
    (net (code "96") (name "Net-(R69-A)") (class "Default")
      (node (ref "R69") (pin "P$3") (pinfunction "A_P$3") (pintype "passive"))
      (node (ref "R77") (pin "2") (pinfunction "2_2") (pintype "passive"))
    )
    (net (code "97") (name "Net-(R70-S)") (class "Default")
      (node (ref "R70") (pin "P$2") (pinfunction "S_P$2") (pintype "passive"))
      (node (ref "R79") (pin "1") (pinfunction "1_1") (pintype "passive"))
    )
    (net (code "98") (name "VCC") (class "Default")
      (node (ref "C19") (pin "1") (pinfunction "1_1") (pintype "passive"))
      (node (ref "C2") (pin "+") (pinfunction "+_+") (pintype "passive"))
      (node (ref "C21") (pin "+") (pinfunction "+_+") (pintype "passive"))
      (node (ref "C24") (pin "1") (pinfunction "1_1") (pintype "passive"))
      (node (ref "C27") (pin "1") (pinfunction "1_1") (pintype "passive"))
      (node (ref "C28") (pin "1") (pinfunction "1_1") (pintype "passive"))
      (node (ref "C4") (pin "1") (pinfunction "1_1") (pintype "passive"))
      (node (ref "C40") (pin "1") (pinfunction "1_1") (pintype "passive"))
      (node (ref "C7") (pin "1") (pinfunction "1_1") (pintype "passive"))
      (node (ref "C8") (pin "1") (pinfunction "1_1") (pintype "passive"))
      (node (ref "IC1") (pin "4") (pinfunction "V+_4") (pintype "power_in"))
      (node (ref "IC10") (pin "4") (pinfunction "V+_4") (pintype "power_in"))
      (node (ref "IC2") (pin "8") (pinfunction "V+_8") (pintype "power_in"))
      (node (ref "IC3") (pin "16") (pinfunction "V+_16") (pintype "power_in"))
      (node (ref "IC4") (pin "4") (pinfunction "V+_4") (pintype "power_in"))
      (node (ref "IC5") (pin "4") (pinfunction "V+_4") (pintype "power_in"))
      (node (ref "IC6") (pin "8") (pinfunction "V+_8") (pintype "power_in"))
      (node (ref "IC7") (pin "16") (pinfunction "V+_16") (pintype "power_in"))
      (node (ref "L2") (pin "1") (pinfunction "1_1") (pintype "passive"))
      (node (ref "R74") (pin "1") (pinfunction "1_1") (pintype "passive"))
    )
    (net (code "99") (name "VEE") (class "Default")
      (node (ref "C1") (pin "-") (pinfunction "-_-") (pintype "passive"))
      (node (ref "C11") (pin "2") (pinfunction "2_2") (pintype "passive"))
      (node (ref "C15") (pin "2") (pinfunction "2_2") (pintype "passive"))
      (node (ref "C20") (pin "2") (pinfunction "2_2") (pintype "passive"))
      (node (ref "C22") (pin "-") (pinfunction "-_-") (pintype "passive"))
      (node (ref "C23") (pin "2") (pinfunction "2_2") (pintype "passive"))
      (node (ref "C3") (pin "2") (pinfunction "2_2") (pintype "passive"))
      (node (ref "C31") (pin "2") (pinfunction "2_2") (pintype "passive"))
      (node (ref "C35") (pin "2") (pinfunction "2_2") (pintype "passive"))
      (node (ref "C39") (pin "2") (pinfunction "2_2") (pintype "passive"))
      (node (ref "D1") (pin "A") (pinfunction "A_A") (pintype "passive"))
      (node (ref "IC1") (pin "11") (pinfunction "V-_11") (pintype "power_in"))
      (node (ref "IC10") (pin "11") (pinfunction "V-_11") (pintype "power_in"))
      (node (ref "IC2") (pin "4") (pinfunction "V-_4") (pintype "power_in"))
      (node (ref "IC3") (pin "9") (pinfunction "V-_9") (pintype "power_in"))
      (node (ref "IC4") (pin "11") (pinfunction "V-_11") (pintype "power_in"))
      (node (ref "IC5") (pin "11") (pinfunction "V-_11") (pintype "power_in"))
      (node (ref "IC6") (pin "4") (pinfunction "V-_4") (pintype "power_in"))
      (node (ref "IC7") (pin "9") (pinfunction "V-_9") (pintype "power_in"))
      (node (ref "L1") (pin "1") (pinfunction "1_1") (pintype "passive"))
      (node (ref "R64") (pin "1") (pinfunction "1_1") (pintype "passive"))
    )
    (net (code "100") (name "unconnected-(IC3E-MODE-Pad1)") (class "Default")
      (node (ref "IC3") (pin "1") (pinfunction "MODE_1") (pintype "input"))
    )
    (net (code "101") (name "unconnected-(IC7E-MODE-Pad1)") (class "Default")
      (node (ref "IC7") (pin "1") (pinfunction "MODE_1") (pintype "input"))
    )
    (net (code "102") (name "unconnected-(J11-2-PadP2)") (class "Default")
      (node (ref "J11") (pin "P2") (pinfunction "2_P2") (pintype "passive"))
    )
  )
)
